# M1705X.net
KiCad netlist of a schematic drawn in EAGLE
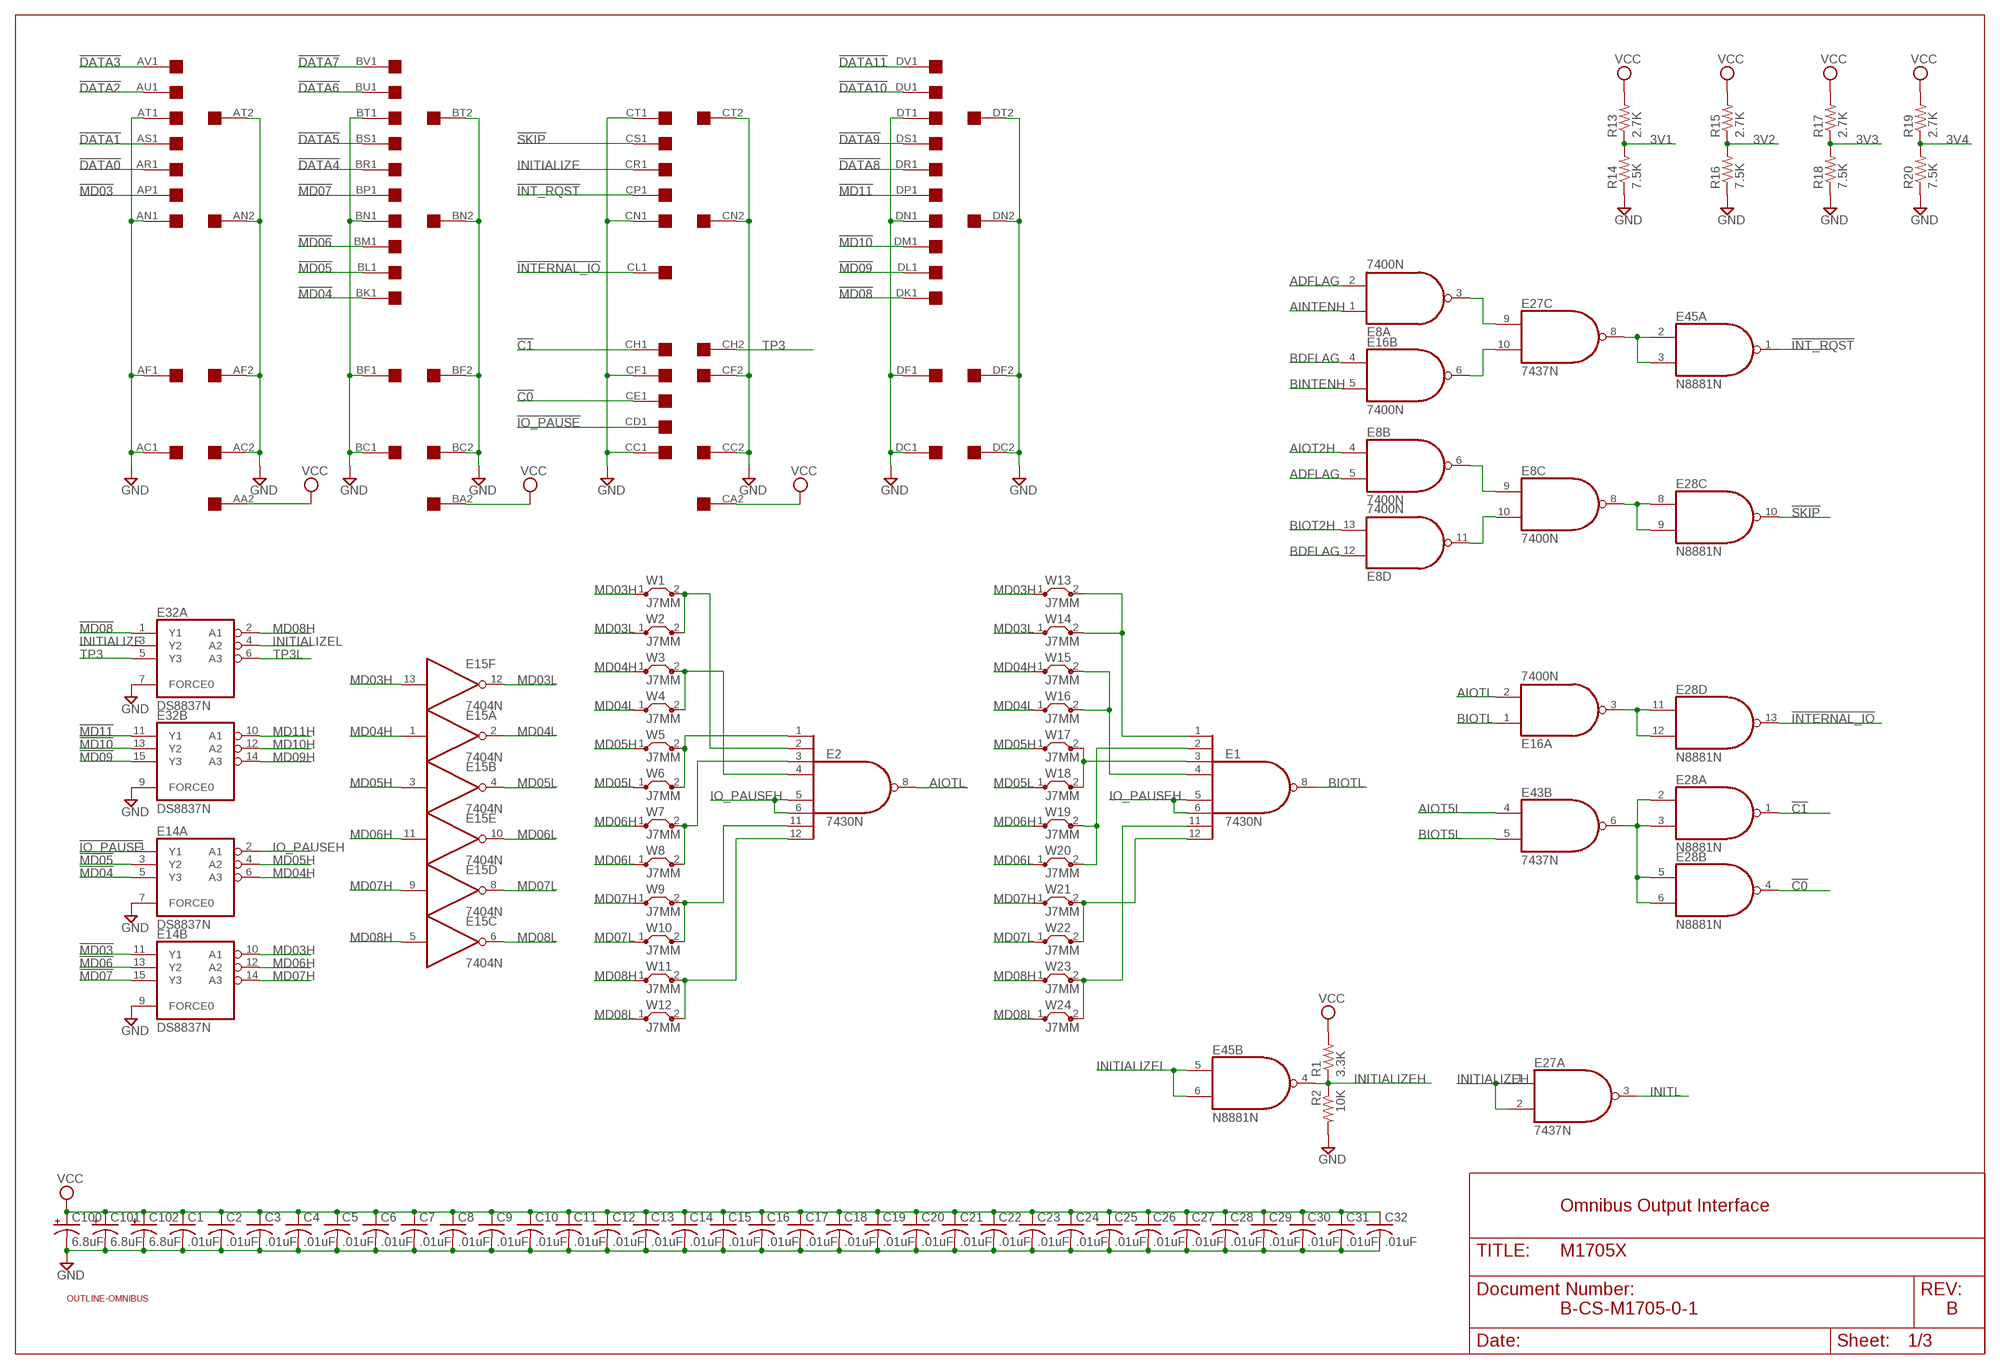
[diagram p0: schematic, sheet 1]
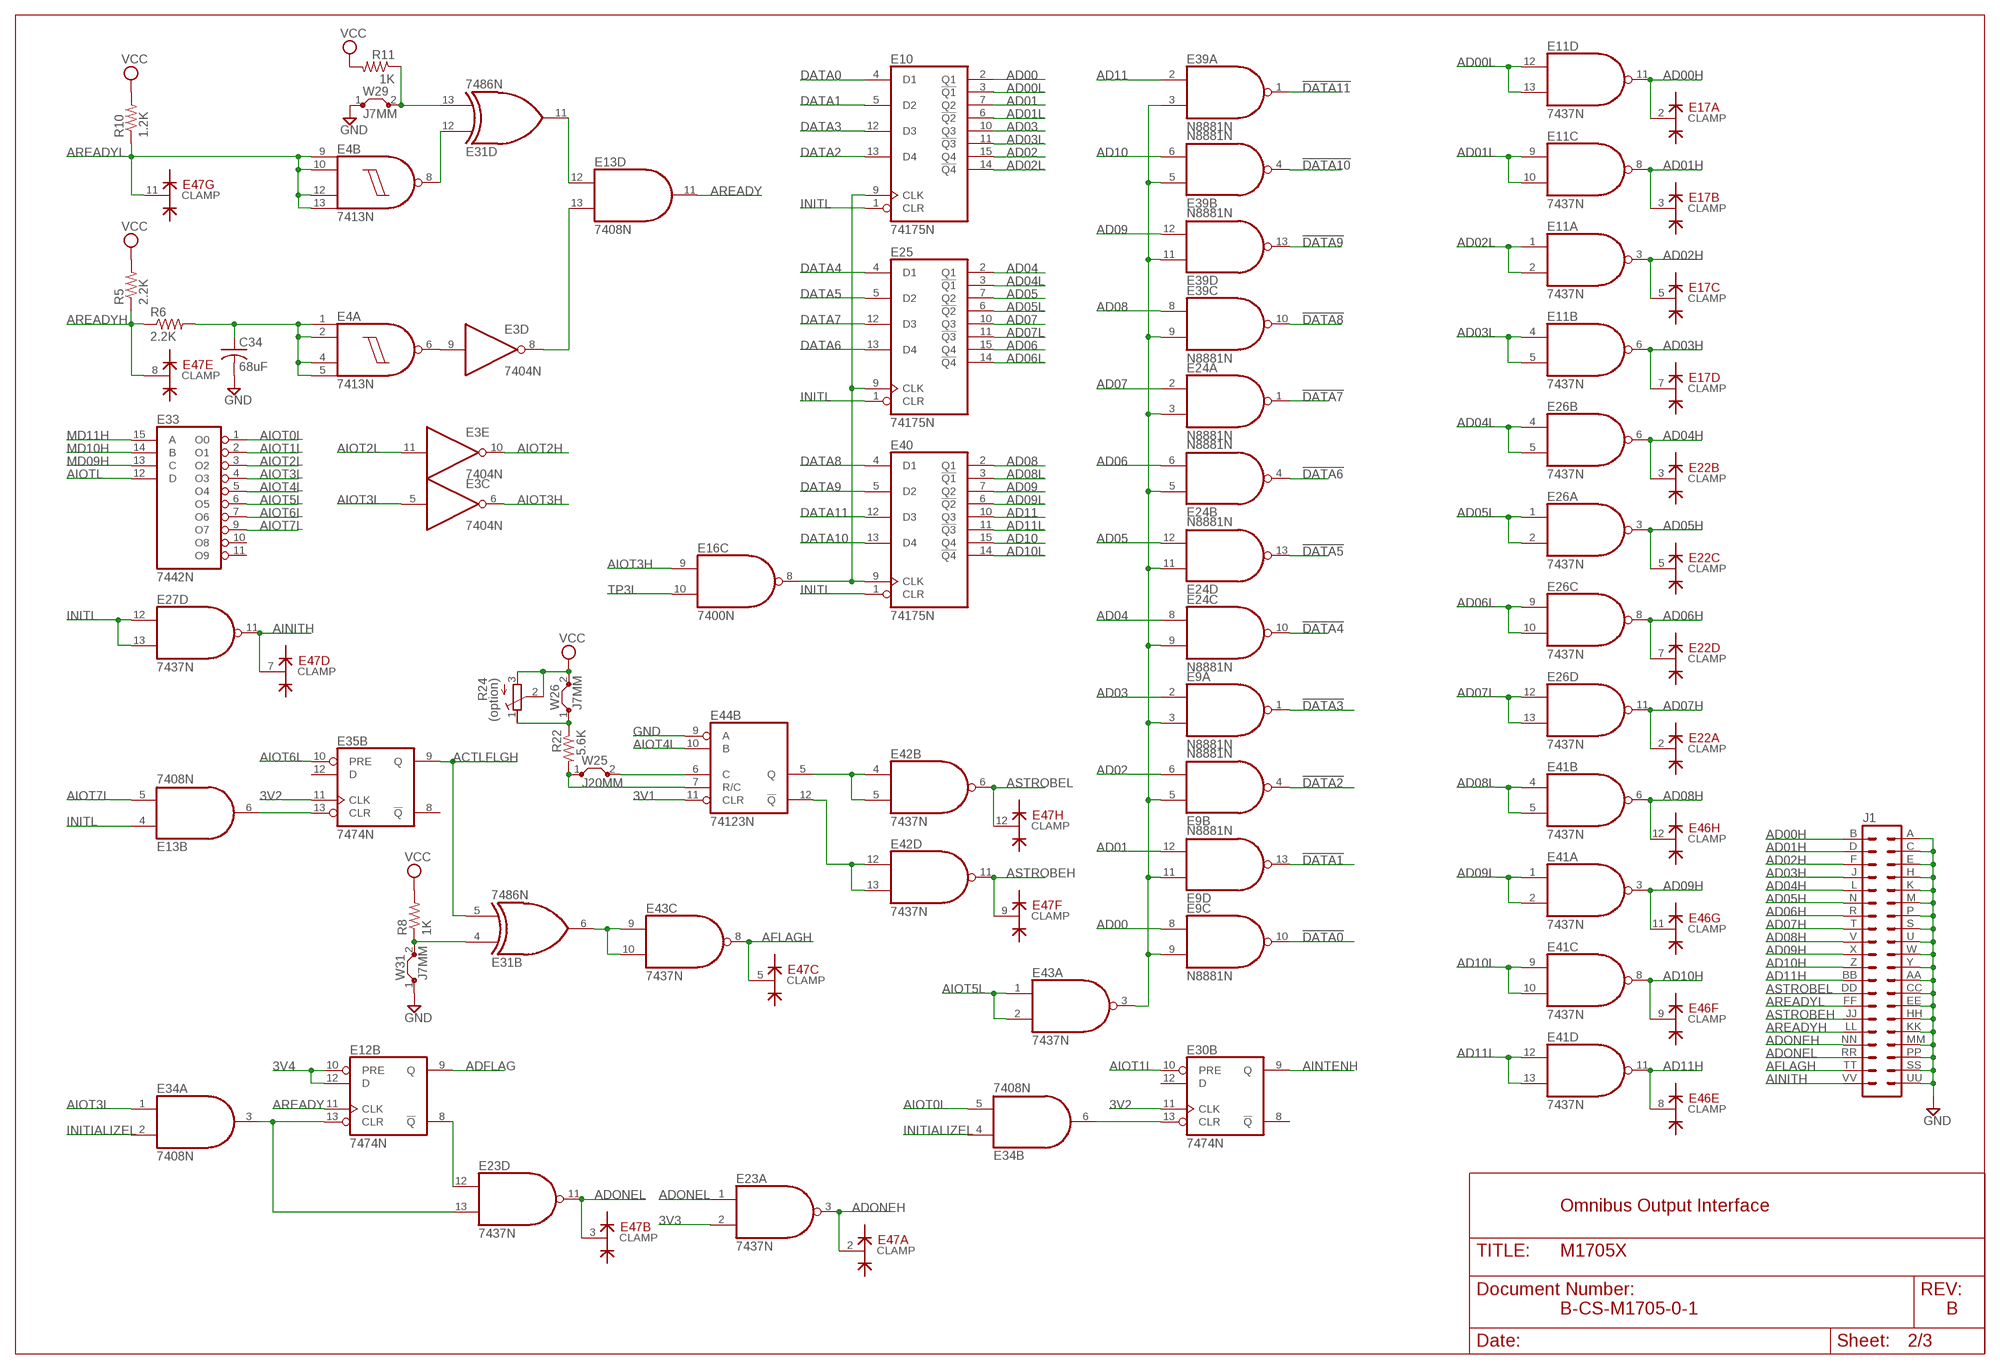
[diagram p1: schematic, sheet 2]
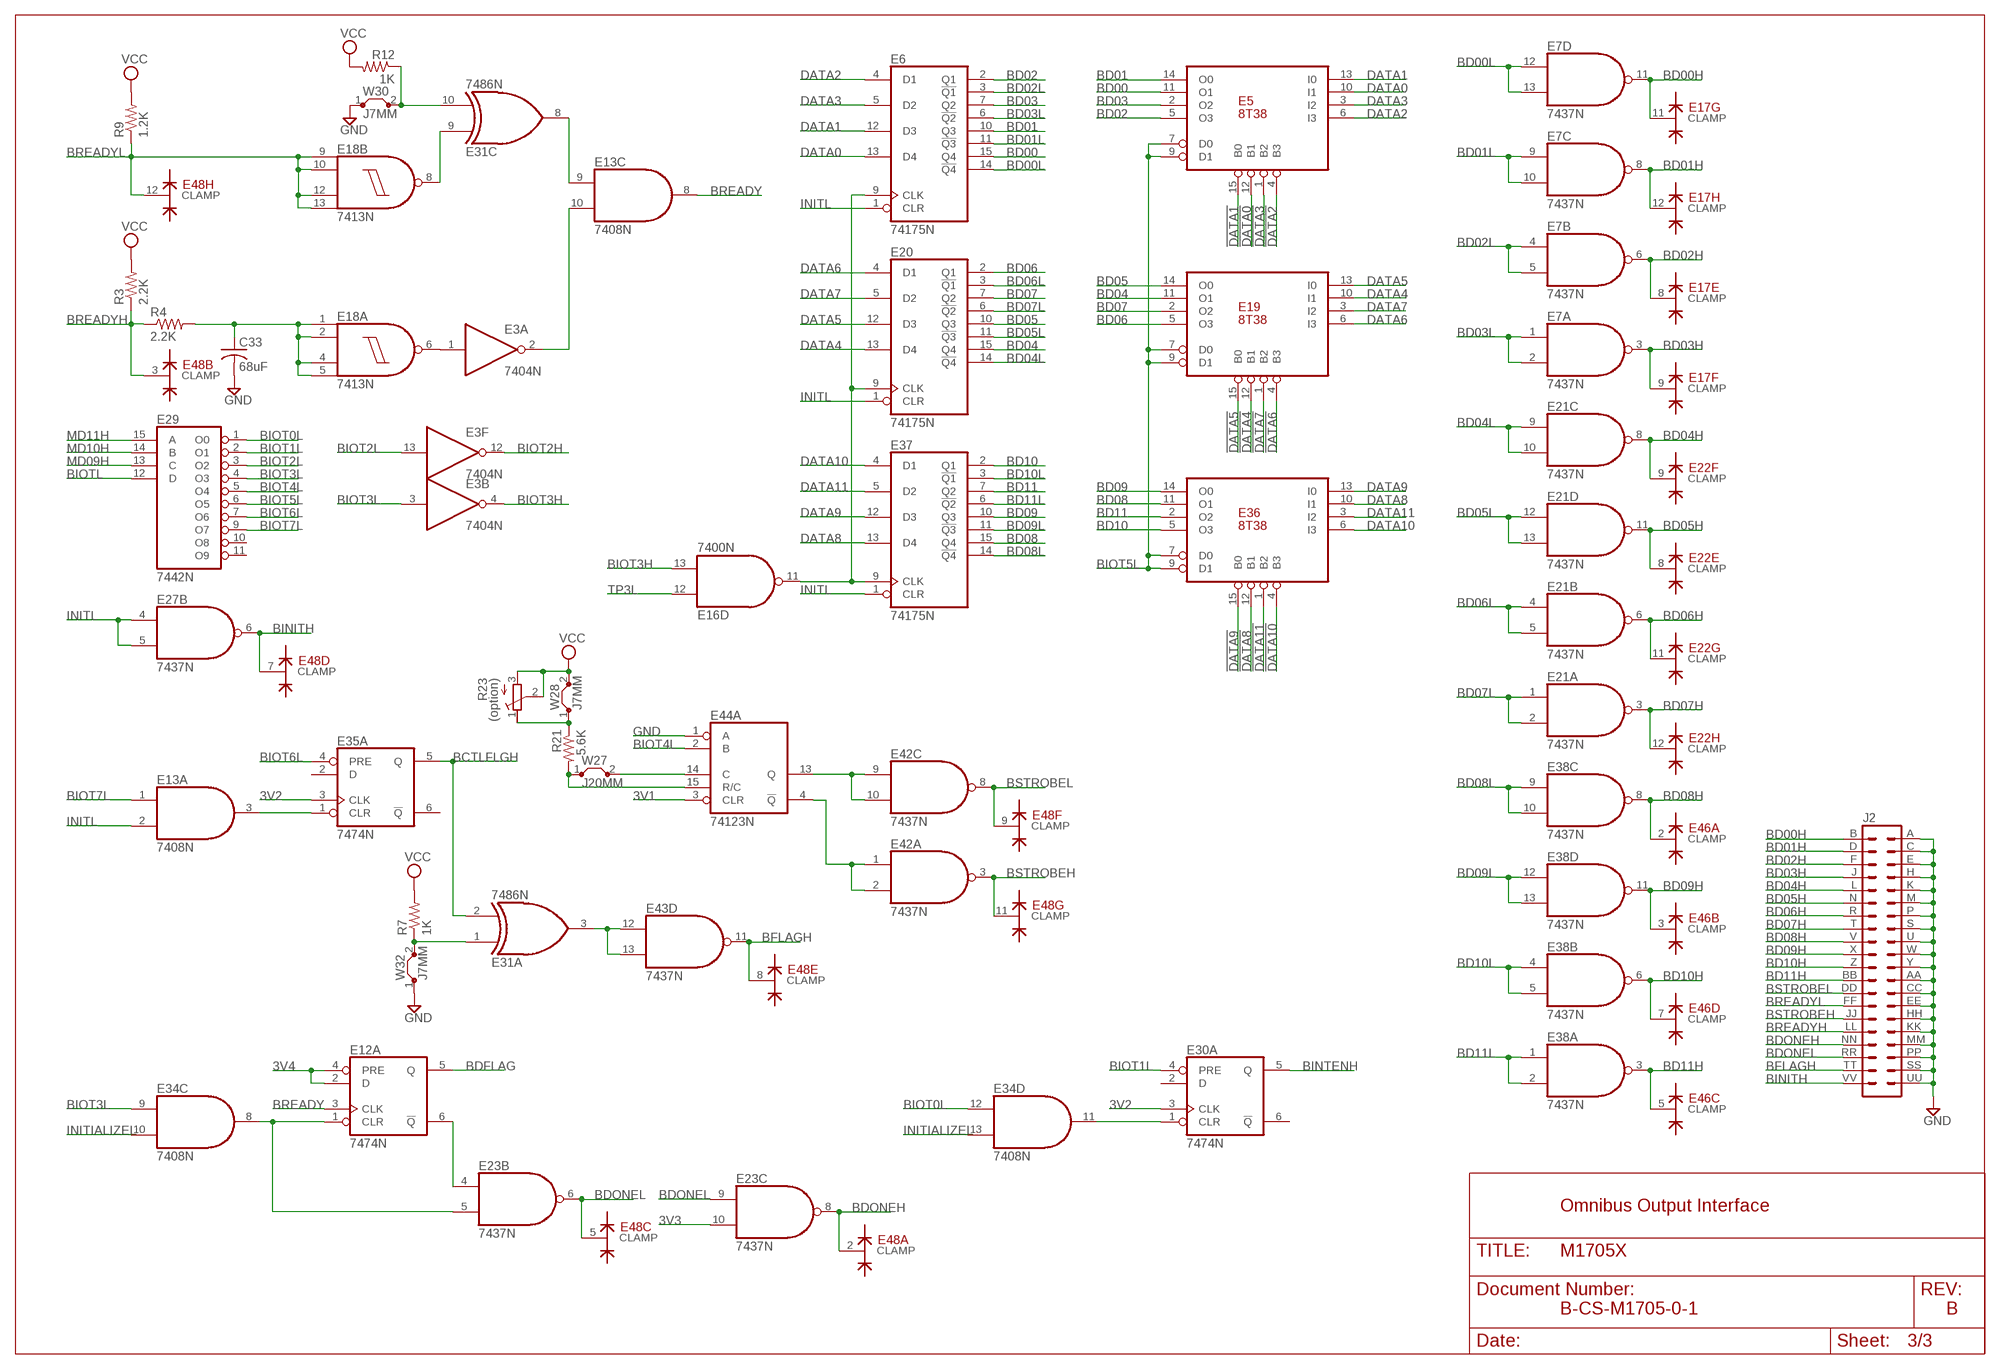
[diagram p2: schematic, sheet 3]

(export (version "E")
  (design (tool "Eeschema 10.0.6"))
  (components
    (comp (ref "C1")
      (value ".01uF")
      (footprint "eagle-import:C075-032X103")
      (libsource (lib "eagle-import") (part "C-US075-032X103"))
    )
    (comp (ref "C2")
      (value ".01uF")
      (footprint "eagle-import:C075-032X103")
      (libsource (lib "eagle-import") (part "C-US075-032X103"))
    )
    (comp (ref "C3")
      (value ".01uF")
      (footprint "eagle-import:C075-032X103")
      (libsource (lib "eagle-import") (part "C-US075-032X103"))
    )
    (comp (ref "C4")
      (value ".01uF")
      (footprint "eagle-import:C075-032X103")
      (libsource (lib "eagle-import") (part "C-US075-032X103"))
    )
    (comp (ref "C5")
      (value ".01uF")
      (footprint "eagle-import:C075-032X103")
      (libsource (lib "eagle-import") (part "C-US075-032X103"))
    )
    (comp (ref "C6")
      (value ".01uF")
      (footprint "eagle-import:C075-032X103")
      (libsource (lib "eagle-import") (part "C-US075-032X103"))
    )
    (comp (ref "C7")
      (value ".01uF")
      (footprint "eagle-import:C075-032X103")
      (libsource (lib "eagle-import") (part "C-US075-032X103"))
    )
    (comp (ref "C8")
      (value ".01uF")
      (footprint "eagle-import:C075-032X103")
      (libsource (lib "eagle-import") (part "C-US075-032X103"))
    )
    (comp (ref "C9")
      (value ".01uF")
      (footprint "eagle-import:C075-032X103")
      (libsource (lib "eagle-import") (part "C-US075-032X103"))
    )
    (comp (ref "C10")
      (value ".01uF")
      (footprint "eagle-import:C075-032X103")
      (libsource (lib "eagle-import") (part "C-US075-032X103"))
    )
    (comp (ref "C11")
      (value ".01uF")
      (footprint "eagle-import:C075-032X103")
      (libsource (lib "eagle-import") (part "C-US075-032X103"))
    )
    (comp (ref "C12")
      (value ".01uF")
      (footprint "eagle-import:C075-032X103")
      (libsource (lib "eagle-import") (part "C-US075-032X103"))
    )
    (comp (ref "C13")
      (value ".01uF")
      (footprint "eagle-import:C075-032X103")
      (libsource (lib "eagle-import") (part "C-US075-032X103"))
    )
    (comp (ref "C14")
      (value ".01uF")
      (footprint "eagle-import:C075-032X103")
      (libsource (lib "eagle-import") (part "C-US075-032X103"))
    )
    (comp (ref "C15")
      (value ".01uF")
      (footprint "eagle-import:C075-032X103")
      (libsource (lib "eagle-import") (part "C-US075-032X103"))
    )
    (comp (ref "C16")
      (value ".01uF")
      (footprint "eagle-import:C075-032X103")
      (libsource (lib "eagle-import") (part "C-US075-032X103"))
    )
    (comp (ref "C17")
      (value ".01uF")
      (footprint "eagle-import:C075-032X103")
      (libsource (lib "eagle-import") (part "C-US075-032X103"))
    )
    (comp (ref "C18")
      (value ".01uF")
      (footprint "eagle-import:C075-032X103")
      (libsource (lib "eagle-import") (part "C-US075-032X103"))
    )
    (comp (ref "C19")
      (value ".01uF")
      (footprint "eagle-import:C075-032X103")
      (libsource (lib "eagle-import") (part "C-US075-032X103"))
    )
    (comp (ref "C20")
      (value ".01uF")
      (footprint "eagle-import:C075-032X103")
      (libsource (lib "eagle-import") (part "C-US075-032X103"))
    )
    (comp (ref "C21")
      (value ".01uF")
      (footprint "eagle-import:C075-032X103")
      (libsource (lib "eagle-import") (part "C-US075-032X103"))
    )
    (comp (ref "C22")
      (value ".01uF")
      (footprint "eagle-import:C075-032X103")
      (libsource (lib "eagle-import") (part "C-US075-032X103"))
    )
    (comp (ref "C23")
      (value ".01uF")
      (footprint "eagle-import:C075-032X103")
      (libsource (lib "eagle-import") (part "C-US075-032X103"))
    )
    (comp (ref "C24")
      (value ".01uF")
      (footprint "eagle-import:C075-032X103")
      (libsource (lib "eagle-import") (part "C-US075-032X103"))
    )
    (comp (ref "C25")
      (value ".01uF")
      (footprint "eagle-import:C075-032X103")
      (libsource (lib "eagle-import") (part "C-US075-032X103"))
    )
    (comp (ref "C26")
      (value ".01uF")
      (footprint "eagle-import:C075-032X103")
      (libsource (lib "eagle-import") (part "C-US075-032X103"))
    )
    (comp (ref "C27")
      (value ".01uF")
      (footprint "eagle-import:C075-032X103")
      (libsource (lib "eagle-import") (part "C-US075-032X103"))
    )
    (comp (ref "C28")
      (value ".01uF")
      (footprint "eagle-import:C075-032X103")
      (libsource (lib "eagle-import") (part "C-US075-032X103"))
    )
    (comp (ref "C29")
      (value ".01uF")
      (footprint "eagle-import:C075-032X103")
      (libsource (lib "eagle-import") (part "C-US075-032X103"))
    )
    (comp (ref "C30")
      (value ".01uF")
      (footprint "eagle-import:C075-032X103")
      (libsource (lib "eagle-import") (part "C-US075-032X103"))
    )
    (comp (ref "C31")
      (value ".01uF")
      (footprint "eagle-import:C075-032X103")
      (libsource (lib "eagle-import") (part "C-US075-032X103"))
    )
    (comp (ref "C32")
      (value ".01uF")
      (footprint "eagle-import:C075-032X103")
      (libsource (lib "eagle-import") (part "C-US075-032X103"))
    )
    (comp (ref "C100")
      (value "6.8uF")
      (footprint "eagle-import:E12-8")
      (libsource (lib "eagle-import") (part "CPOL-USE20-8AXIAL"))
    )
    (comp (ref "C101")
      (value "6.8uF")
      (footprint "eagle-import:E12-8")
      (libsource (lib "eagle-import") (part "CPOL-USE20-8AXIAL"))
    )
    (comp (ref "C102")
      (value "6.8uF")
      (footprint "eagle-import:E12-8")
      (libsource (lib "eagle-import") (part "CPOL-USE20-8AXIAL"))
    )
    (comp (ref "E1")
      (value "7430N")
      (footprint "eagle-import:DIL14")
      (libsource (lib "eagle-import") (part "7430N"))
    )
    (comp (ref "E2")
      (value "7430N")
      (footprint "eagle-import:DIL14")
      (libsource (lib "eagle-import") (part "7430N"))
    )
    (comp (ref "E8")
      (value "7400N")
      (footprint "eagle-import:DIL14")
      (libsource (lib "eagle-import") (part "7400N"))
    )
    (comp (ref "E14")
      (value "DS8837N")
      (footprint "eagle-import:DIL16")
      (libsource (lib "eagle-import") (part "DS8837N"))
    )
    (comp (ref "E15")
      (value "7404N")
      (footprint "eagle-import:DIL14")
      (libsource (lib "eagle-import") (part "7404N"))
    )
    (comp (ref "E16")
      (value "7400N")
      (footprint "eagle-import:DIL14")
      (libsource (lib "eagle-import") (part "7400N"))
    )
    (comp (ref "E27")
      (value "7437N")
      (footprint "eagle-import:DIL14")
      (libsource (lib "eagle-import") (part "7437N"))
    )
    (comp (ref "E28")
      (value "N8881N")
      (footprint "eagle-import:DIL14")
      (libsource (lib "eagle-import") (part "N8881N"))
    )
    (comp (ref "E32")
      (value "DS8837N")
      (footprint "eagle-import:DIL16")
      (libsource (lib "eagle-import") (part "DS8837N"))
    )
    (comp (ref "E43")
      (value "7437N")
      (footprint "eagle-import:DIL14")
      (libsource (lib "eagle-import") (part "7437N"))
    )
    (comp (ref "E45")
      (value "N8881N")
      (footprint "eagle-import:DIL14")
      (libsource (lib "eagle-import") (part "N8881N"))
    )
    (comp (ref "R1")
      (value "3.3K")
      (footprint "eagle-import:0207_10")
      (libsource (lib "eagle-import") (part "R-US_0207/10"))
    )
    (comp (ref "R2")
      (value "10K")
      (footprint "eagle-import:0207_10")
      (libsource (lib "eagle-import") (part "R-US_0207/10"))
    )
    (comp (ref "R13")
      (value "2.7K")
      (footprint "eagle-import:0207_10")
      (libsource (lib "eagle-import") (part "R-US_0207/10"))
    )
    (comp (ref "R14")
      (value "7.5K")
      (footprint "eagle-import:0207_10")
      (libsource (lib "eagle-import") (part "R-US_0207/10"))
    )
    (comp (ref "R15")
      (value "2.7K")
      (footprint "eagle-import:0207_10")
      (libsource (lib "eagle-import") (part "R-US_0207/10"))
    )
    (comp (ref "R16")
      (value "7.5K")
      (footprint "eagle-import:0207_10")
      (libsource (lib "eagle-import") (part "R-US_0207/10"))
    )
    (comp (ref "R17")
      (value "2.7K")
      (footprint "eagle-import:0207_10")
      (libsource (lib "eagle-import") (part "R-US_0207/10"))
    )
    (comp (ref "R18")
      (value "7.5K")
      (footprint "eagle-import:0207_10")
      (libsource (lib "eagle-import") (part "R-US_0207/10"))
    )
    (comp (ref "R19")
      (value "2.7K")
      (footprint "eagle-import:0207_10")
      (libsource (lib "eagle-import") (part "R-US_0207/10"))
    )
    (comp (ref "R20")
      (value "7.5K")
      (footprint "eagle-import:0207_10")
      (libsource (lib "eagle-import") (part "R-US_0207/10"))
    )
    (comp (ref "U$2")
      (value "QUAD")
      (footprint "eagle-import:EDGE-CON8")
      (libsource (lib "eagle-import") (part "QUAD"))
    )
    (comp (ref "U$4")
      (value "OUTLINE-OMNIBUS")
      (footprint "eagle-import:OMNIBUS")
      (libsource (lib "eagle-import") (part "OUTLINE-OMNIBUS"))
    )
    (comp (ref "W1")
      (value "J7MM")
      (footprint "eagle-import:07")
      (libsource (lib "eagle-import") (part "J7MM"))
    )
    (comp (ref "W2")
      (value "J7MM")
      (footprint "eagle-import:07")
      (libsource (lib "eagle-import") (part "J7MM"))
    )
    (comp (ref "W3")
      (value "J7MM")
      (footprint "eagle-import:07")
      (libsource (lib "eagle-import") (part "J7MM"))
    )
    (comp (ref "W4")
      (value "J7MM")
      (footprint "eagle-import:07")
      (libsource (lib "eagle-import") (part "J7MM"))
    )
    (comp (ref "W5")
      (value "J7MM")
      (footprint "eagle-import:07")
      (libsource (lib "eagle-import") (part "J7MM"))
    )
    (comp (ref "W6")
      (value "J7MM")
      (footprint "eagle-import:07")
      (libsource (lib "eagle-import") (part "J7MM"))
    )
    (comp (ref "W7")
      (value "J7MM")
      (footprint "eagle-import:07")
      (libsource (lib "eagle-import") (part "J7MM"))
    )
    (comp (ref "W8")
      (value "J7MM")
      (footprint "eagle-import:07")
      (libsource (lib "eagle-import") (part "J7MM"))
    )
    (comp (ref "W9")
      (value "J7MM")
      (footprint "eagle-import:07")
      (libsource (lib "eagle-import") (part "J7MM"))
    )
    (comp (ref "W10")
      (value "J7MM")
      (footprint "eagle-import:07")
      (libsource (lib "eagle-import") (part "J7MM"))
    )
    (comp (ref "W11")
      (value "J7MM")
      (footprint "eagle-import:07")
      (libsource (lib "eagle-import") (part "J7MM"))
    )
    (comp (ref "W12")
      (value "J7MM")
      (footprint "eagle-import:07")
      (libsource (lib "eagle-import") (part "J7MM"))
    )
    (comp (ref "W13")
      (value "J7MM")
      (footprint "eagle-import:07")
      (libsource (lib "eagle-import") (part "J7MM"))
    )
    (comp (ref "W14")
      (value "J7MM")
      (footprint "eagle-import:07")
      (libsource (lib "eagle-import") (part "J7MM"))
    )
    (comp (ref "W15")
      (value "J7MM")
      (footprint "eagle-import:07")
      (libsource (lib "eagle-import") (part "J7MM"))
    )
    (comp (ref "W16")
      (value "J7MM")
      (footprint "eagle-import:07")
      (libsource (lib "eagle-import") (part "J7MM"))
    )
    (comp (ref "W17")
      (value "J7MM")
      (footprint "eagle-import:07")
      (libsource (lib "eagle-import") (part "J7MM"))
    )
    (comp (ref "W18")
      (value "J7MM")
      (footprint "eagle-import:07")
      (libsource (lib "eagle-import") (part "J7MM"))
    )
    (comp (ref "W19")
      (value "J7MM")
      (footprint "eagle-import:07")
      (libsource (lib "eagle-import") (part "J7MM"))
    )
    (comp (ref "W20")
      (value "J7MM")
      (footprint "eagle-import:07")
      (libsource (lib "eagle-import") (part "J7MM"))
    )
    (comp (ref "W21")
      (value "J7MM")
      (footprint "eagle-import:07")
      (libsource (lib "eagle-import") (part "J7MM"))
    )
    (comp (ref "W22")
      (value "J7MM")
      (footprint "eagle-import:07")
      (libsource (lib "eagle-import") (part "J7MM"))
    )
    (comp (ref "W23")
      (value "J7MM")
      (footprint "eagle-import:07")
      (libsource (lib "eagle-import") (part "J7MM"))
    )
    (comp (ref "W24")
      (value "J7MM")
      (footprint "eagle-import:07")
      (libsource (lib "eagle-import") (part "J7MM"))
    )
    (comp (ref "C34")
      (value "68uF")
      (footprint "eagle-import:C102-043X133")
      (libsource (lib "eagle-import") (part "C-US102-043X133"))
    )
    (comp (ref "E3")
      (value "7404N")
      (footprint "eagle-import:DIL14")
      (libsource (lib "eagle-import") (part "7404N"))
    )
    (comp (ref "E4")
      (value "7413N")
      (footprint "eagle-import:DIL14")
      (libsource (lib "eagle-import") (part "7413N"))
    )
    (comp (ref "E9")
      (value "N8881N")
      (footprint "eagle-import:DIL14")
      (libsource (lib "eagle-import") (part "N8881N"))
    )
    (comp (ref "E10")
      (value "74175N")
      (footprint "eagle-import:DIL16")
      (libsource (lib "eagle-import") (part "74175N"))
    )
    (comp (ref "E11")
      (value "7437N")
      (footprint "eagle-import:DIL14")
      (libsource (lib "eagle-import") (part "7437N"))
    )
    (comp (ref "E12")
      (value "7474N")
      (footprint "eagle-import:DIL14")
      (libsource (lib "eagle-import") (part "7474NS"))
    )
    (comp (ref "E13")
      (value "7408N")
      (footprint "eagle-import:DIL14")
      (libsource (lib "eagle-import") (part "7408NLS"))
    )
    (comp (ref "E17")
      (value "DEC2501")
      (footprint "eagle-import:DIL14")
      (libsource (lib "eagle-import") (part "DEC2501"))
    )
    (comp (ref "E22")
      (value "DEC2501")
      (footprint "eagle-import:DIL14")
      (libsource (lib "eagle-import") (part "DEC2501"))
    )
    (comp (ref "E23")
      (value "7437N")
      (footprint "eagle-import:DIL14")
      (libsource (lib "eagle-import") (part "7437N"))
    )
    (comp (ref "E24")
      (value "N8881N")
      (footprint "eagle-import:DIL14")
      (libsource (lib "eagle-import") (part "N8881N"))
    )
    (comp (ref "E25")
      (value "74175N")
      (footprint "eagle-import:DIL16")
      (libsource (lib "eagle-import") (part "74175N"))
    )
    (comp (ref "E26")
      (value "7437N")
      (footprint "eagle-import:DIL14")
      (libsource (lib "eagle-import") (part "7437N"))
    )
    (comp (ref "E30")
      (value "7474N")
      (footprint "eagle-import:DIL14")
      (libsource (lib "eagle-import") (part "7474NS"))
    )
    (comp (ref "E31")
      (value "7486N")
      (footprint "eagle-import:DIL14")
      (libsource (lib "eagle-import") (part "7486N"))
    )
    (comp (ref "E33")
      (value "7442N")
      (footprint "eagle-import:DIL16")
      (libsource (lib "eagle-import") (part "7442NLS"))
    )
    (comp (ref "E34")
      (value "7408N")
      (footprint "eagle-import:DIL14")
      (libsource (lib "eagle-import") (part "7408NLS"))
    )
    (comp (ref "E35")
      (value "7474N")
      (footprint "eagle-import:DIL14")
      (libsource (lib "eagle-import") (part "7474NS"))
    )
    (comp (ref "E39")
      (value "N8881N")
      (footprint "eagle-import:DIL14")
      (libsource (lib "eagle-import") (part "N8881N"))
    )
    (comp (ref "E40")
      (value "74175N")
      (footprint "eagle-import:DIL16")
      (libsource (lib "eagle-import") (part "74175N"))
    )
    (comp (ref "E41")
      (value "7437N")
      (footprint "eagle-import:DIL14")
      (libsource (lib "eagle-import") (part "7437N"))
    )
    (comp (ref "E42")
      (value "7437N")
      (footprint "eagle-import:DIL14")
      (libsource (lib "eagle-import") (part "7437N"))
    )
    (comp (ref "E44")
      (value "74123N")
      (footprint "eagle-import:DIL16")
      (libsource (lib "eagle-import") (part "74123N"))
    )
    (comp (ref "E46")
      (value "DEC2501")
      (footprint "eagle-import:DIL14")
      (libsource (lib "eagle-import") (part "DEC2501"))
    )
    (comp (ref "E47")
      (value "DEC2501")
      (footprint "eagle-import:DIL14")
      (libsource (lib "eagle-import") (part "DEC2501"))
    )
    (comp (ref "J1")
      (value "DEC40PINH")
      (footprint "eagle-import:DEC40PINH")
      (libsource (lib "eagle-import") (part "DEC40PINH"))
    )
    (comp (ref "R5")
      (value "2.2K")
      (footprint "eagle-import:0207_10")
      (libsource (lib "eagle-import") (part "R-US_0207/10"))
    )
    (comp (ref "R6")
      (value "2.2K")
      (footprint "eagle-import:0207_10")
      (libsource (lib "eagle-import") (part "R-US_0207/10"))
    )
    (comp (ref "R8")
      (value "1K")
      (footprint "eagle-import:0207_10")
      (libsource (lib "eagle-import") (part "R-US_0207/10"))
    )
    (comp (ref "R10")
      (value "1.2K")
      (footprint "eagle-import:0207_10")
      (libsource (lib "eagle-import") (part "R-US_0207/10"))
    )
    (comp (ref "R11")
      (value "1K")
      (footprint "eagle-import:0207_10")
      (libsource (lib "eagle-import") (part "R-US_0207/10"))
    )
    (comp (ref "R22")
      (value "5.6K")
      (footprint "eagle-import:0207_10")
      (libsource (lib "eagle-import") (part "R-US_0207/10"))
    )
    (comp (ref "R24")
      (value "(option)")
      (footprint "eagle-import:3006Y")
      (libsource (lib "eagle-import") (part "275P"))
    )
    (comp (ref "W25")
      (value "J20MM")
      (footprint "eagle-import:20")
      (libsource (lib "eagle-import") (part "J20MM"))
    )
    (comp (ref "W26")
      (value "J7MM")
      (footprint "eagle-import:07")
      (libsource (lib "eagle-import") (part "J7MM"))
    )
    (comp (ref "W29")
      (value "J7MM")
      (footprint "eagle-import:07")
      (libsource (lib "eagle-import") (part "J7MM"))
    )
    (comp (ref "W31")
      (value "J7MM")
      (footprint "eagle-import:07")
      (libsource (lib "eagle-import") (part "J7MM"))
    )
    (comp (ref "C33")
      (value "68uF")
      (footprint "eagle-import:C102-043X133")
      (libsource (lib "eagle-import") (part "C-US102-043X133"))
    )
    (comp (ref "E5")
      (value "8T38")
      (footprint "eagle-import:DIL16")
      (libsource (lib "eagle-import") (part "DS8641N"))
    )
    (comp (ref "E6")
      (value "74175N")
      (footprint "eagle-import:DIL16")
      (libsource (lib "eagle-import") (part "74175N"))
    )
    (comp (ref "E7")
      (value "7437N")
      (footprint "eagle-import:DIL14")
      (libsource (lib "eagle-import") (part "7437N"))
    )
    (comp (ref "E18")
      (value "7413N")
      (footprint "eagle-import:DIL14")
      (libsource (lib "eagle-import") (part "7413N"))
    )
    (comp (ref "E19")
      (value "8T38")
      (footprint "eagle-import:DIL16")
      (libsource (lib "eagle-import") (part "DS8641N"))
    )
    (comp (ref "E20")
      (value "74175N")
      (footprint "eagle-import:DIL16")
      (libsource (lib "eagle-import") (part "74175N"))
    )
    (comp (ref "E21")
      (value "7437N")
      (footprint "eagle-import:DIL14")
      (libsource (lib "eagle-import") (part "7437N"))
    )
    (comp (ref "E29")
      (value "7442N")
      (footprint "eagle-import:DIL16")
      (libsource (lib "eagle-import") (part "7442NLS"))
    )
    (comp (ref "E36")
      (value "8T38")
      (footprint "eagle-import:DIL16")
      (libsource (lib "eagle-import") (part "DS8641N"))
    )
    (comp (ref "E37")
      (value "74175N")
      (footprint "eagle-import:DIL16")
      (libsource (lib "eagle-import") (part "74175N"))
    )
    (comp (ref "E38")
      (value "7437N")
      (footprint "eagle-import:DIL14")
      (libsource (lib "eagle-import") (part "7437N"))
    )
    (comp (ref "E48")
      (value "DEC2501")
      (footprint "eagle-import:DIL14")
      (libsource (lib "eagle-import") (part "DEC2501"))
    )
    (comp (ref "J2")
      (value "DEC40PINH")
      (footprint "eagle-import:DEC40PINH")
      (libsource (lib "eagle-import") (part "DEC40PINH"))
    )
    (comp (ref "R3")
      (value "2.2K")
      (footprint "eagle-import:0207_10")
      (libsource (lib "eagle-import") (part "R-US_0207/10"))
    )
    (comp (ref "R4")
      (value "2.2K")
      (footprint "eagle-import:0207_10")
      (libsource (lib "eagle-import") (part "R-US_0207/10"))
    )
    (comp (ref "R7")
      (value "1K")
      (footprint "eagle-import:0207_10")
      (libsource (lib "eagle-import") (part "R-US_0207/10"))
    )
    (comp (ref "R9")
      (value "1.2K")
      (footprint "eagle-import:0207_10")
      (libsource (lib "eagle-import") (part "R-US_0207/10"))
    )
    (comp (ref "R12")
      (value "1K")
      (footprint "eagle-import:0207_10")
      (libsource (lib "eagle-import") (part "R-US_0207/10"))
    )
    (comp (ref "R21")
      (value "5.6K")
      (footprint "eagle-import:0207_10")
      (libsource (lib "eagle-import") (part "R-US_0207/10"))
    )
    (comp (ref "R23")
      (value "(option)")
      (footprint "eagle-import:3006Y")
      (libsource (lib "eagle-import") (part "275P"))
    )
    (comp (ref "W27")
      (value "J20MM")
      (footprint "eagle-import:20")
      (libsource (lib "eagle-import") (part "J20MM"))
    )
    (comp (ref "W28")
      (value "J7MM")
      (footprint "eagle-import:07")
      (libsource (lib "eagle-import") (part "J7MM"))
    )
    (comp (ref "W30")
      (value "J7MM")
      (footprint "eagle-import:07")
      (libsource (lib "eagle-import") (part "J7MM"))
    )
    (comp (ref "W32")
      (value "J7MM")
      (footprint "eagle-import:07")
      (libsource (lib "eagle-import") (part "J7MM"))
    )
  )
  (nets
    (net (code "1") (name "3V1") (class "Default")
      (node (ref "E44") (pin "11") (pinfunction "CLR_11") (pintype "input"))
      (node (ref "E44") (pin "3") (pinfunction "CLR_3") (pintype "input"))
      (node (ref "R13") (pin "1") (pinfunction "1_1") (pintype "passive"))
      (node (ref "R14") (pin "2") (pinfunction "2_2") (pintype "passive"))
    )
    (net (code "2") (name "3V2") (class "Default")
      (node (ref "E30") (pin "11") (pinfunction "CLK_11") (pintype "input"))
      (node (ref "E30") (pin "3") (pinfunction "CLK_3") (pintype "input"))
      (node (ref "E35") (pin "11") (pinfunction "CLK_11") (pintype "input"))
      (node (ref "E35") (pin "3") (pinfunction "CLK_3") (pintype "input"))
      (node (ref "R15") (pin "1") (pinfunction "1_1") (pintype "passive"))
      (node (ref "R16") (pin "2") (pinfunction "2_2") (pintype "passive"))
    )
    (net (code "3") (name "3V3") (class "Default")
      (node (ref "E23") (pin "10") (pinfunction "I1_10") (pintype "input"))
      (node (ref "E23") (pin "2") (pinfunction "I1_2") (pintype "input"))
      (node (ref "R17") (pin "1") (pinfunction "1_1") (pintype "passive"))
      (node (ref "R18") (pin "2") (pinfunction "2_2") (pintype "passive"))
    )
    (net (code "4") (name "3V4") (class "Default")
      (node (ref "E12") (pin "10") (pinfunction "PRE_10") (pintype "input"))
      (node (ref "E12") (pin "12") (pinfunction "D_12") (pintype "input"))
      (node (ref "E12") (pin "2") (pinfunction "D_2") (pintype "input"))
      (node (ref "E12") (pin "4") (pinfunction "PRE_4") (pintype "input"))
      (node (ref "R19") (pin "1") (pinfunction "1_1") (pintype "passive"))
      (node (ref "R20") (pin "2") (pinfunction "2_2") (pintype "passive"))
    )
    (net (code "5") (name "ACTLFLGH") (class "Default")
      (node (ref "E31") (pin "5") (pinfunction "I1_5") (pintype "input"))
      (node (ref "E35") (pin "9") (pinfunction "Q_9") (pintype "output"))
    )
    (net (code "6") (name "AD00") (class "Default")
      (node (ref "E10") (pin "2") (pinfunction "Q1_2") (pintype "output"))
      (node (ref "E9") (pin "8") (pinfunction "I0_8") (pintype "input"))
    )
    (net (code "7") (name "AD00H") (class "Default")
      (node (ref "E11") (pin "11") (pinfunction "O_11") (pintype "output"))
      (node (ref "E17") (pin "2") (pinfunction "CLAMP_2") (pintype "input"))
      (node (ref "J1") (pin "B") (pinfunction "2_B") (pintype "bidirectional"))
    )
    (net (code "8") (name "AD00L") (class "Default")
      (node (ref "E10") (pin "3") (pinfunction "~{Q1}_3") (pintype "output"))
      (node (ref "E11") (pin "12") (pinfunction "I0_12") (pintype "input"))
      (node (ref "E11") (pin "13") (pinfunction "I1_13") (pintype "input"))
    )
    (net (code "9") (name "AD01") (class "Default")
      (node (ref "E10") (pin "7") (pinfunction "Q2_7") (pintype "output"))
      (node (ref "E9") (pin "12") (pinfunction "I1_12") (pintype "input"))
    )
    (net (code "10") (name "AD01H") (class "Default")
      (node (ref "E11") (pin "8") (pinfunction "O_8") (pintype "output"))
      (node (ref "E17") (pin "3") (pinfunction "CLAMP_3") (pintype "input"))
      (node (ref "J1") (pin "D") (pinfunction "4_D") (pintype "bidirectional"))
    )
    (net (code "11") (name "AD01L") (class "Default")
      (node (ref "E10") (pin "6") (pinfunction "~{Q2}_6") (pintype "output"))
      (node (ref "E11") (pin "10") (pinfunction "I1_10") (pintype "input"))
      (node (ref "E11") (pin "9") (pinfunction "I0_9") (pintype "input"))
    )
    (net (code "12") (name "AD02") (class "Default")
      (node (ref "E10") (pin "15") (pinfunction "Q4_15") (pintype "output"))
      (node (ref "E9") (pin "6") (pinfunction "I1_6") (pintype "input"))
    )
    (net (code "13") (name "AD02H") (class "Default")
      (node (ref "E11") (pin "3") (pinfunction "O_3") (pintype "output"))
      (node (ref "E17") (pin "5") (pinfunction "CLAMP_5") (pintype "input"))
      (node (ref "J1") (pin "F") (pinfunction "6_F") (pintype "bidirectional"))
    )
    (net (code "14") (name "AD02L") (class "Default")
      (node (ref "E10") (pin "14") (pinfunction "~{Q4}_14") (pintype "output"))
      (node (ref "E11") (pin "1") (pinfunction "I0_1") (pintype "input"))
      (node (ref "E11") (pin "2") (pinfunction "I1_2") (pintype "input"))
    )
    (net (code "15") (name "AD03") (class "Default")
      (node (ref "E10") (pin "10") (pinfunction "Q3_10") (pintype "output"))
      (node (ref "E9") (pin "2") (pinfunction "I0_2") (pintype "input"))
    )
    (net (code "16") (name "AD03H") (class "Default")
      (node (ref "E11") (pin "6") (pinfunction "O_6") (pintype "output"))
      (node (ref "E17") (pin "7") (pinfunction "CLAMP_7") (pintype "input"))
      (node (ref "J1") (pin "J") (pinfunction "8_J") (pintype "bidirectional"))
    )
    (net (code "17") (name "AD03L") (class "Default")
      (node (ref "E10") (pin "11") (pinfunction "~{Q3}_11") (pintype "output"))
      (node (ref "E11") (pin "4") (pinfunction "I0_4") (pintype "input"))
      (node (ref "E11") (pin "5") (pinfunction "I1_5") (pintype "input"))
    )
    (net (code "18") (name "AD04") (class "Default")
      (node (ref "E24") (pin "8") (pinfunction "I0_8") (pintype "input"))
      (node (ref "E25") (pin "2") (pinfunction "Q1_2") (pintype "output"))
    )
    (net (code "19") (name "AD04H") (class "Default")
      (node (ref "E22") (pin "3") (pinfunction "CLAMP_3") (pintype "input"))
      (node (ref "E26") (pin "6") (pinfunction "O_6") (pintype "output"))
      (node (ref "J1") (pin "L") (pinfunction "10_L") (pintype "bidirectional"))
    )
    (net (code "20") (name "AD04L") (class "Default")
      (node (ref "E25") (pin "3") (pinfunction "~{Q1}_3") (pintype "output"))
      (node (ref "E26") (pin "4") (pinfunction "I0_4") (pintype "input"))
      (node (ref "E26") (pin "5") (pinfunction "I1_5") (pintype "input"))
    )
    (net (code "21") (name "AD05") (class "Default")
      (node (ref "E24") (pin "12") (pinfunction "I1_12") (pintype "input"))
      (node (ref "E25") (pin "7") (pinfunction "Q2_7") (pintype "output"))
    )
    (net (code "22") (name "AD05H") (class "Default")
      (node (ref "E22") (pin "5") (pinfunction "CLAMP_5") (pintype "input"))
      (node (ref "E26") (pin "3") (pinfunction "O_3") (pintype "output"))
      (node (ref "J1") (pin "N") (pinfunction "12_N") (pintype "bidirectional"))
    )
    (net (code "23") (name "AD05L") (class "Default")
      (node (ref "E25") (pin "6") (pinfunction "~{Q2}_6") (pintype "output"))
      (node (ref "E26") (pin "1") (pinfunction "I0_1") (pintype "input"))
      (node (ref "E26") (pin "2") (pinfunction "I1_2") (pintype "input"))
    )
    (net (code "24") (name "AD06") (class "Default")
      (node (ref "E24") (pin "6") (pinfunction "I1_6") (pintype "input"))
      (node (ref "E25") (pin "15") (pinfunction "Q4_15") (pintype "output"))
    )
    (net (code "25") (name "AD06H") (class "Default")
      (node (ref "E22") (pin "7") (pinfunction "CLAMP_7") (pintype "input"))
      (node (ref "E26") (pin "8") (pinfunction "O_8") (pintype "output"))
      (node (ref "J1") (pin "R") (pinfunction "14_R") (pintype "bidirectional"))
    )
    (net (code "26") (name "AD06L") (class "Default")
      (node (ref "E25") (pin "14") (pinfunction "~{Q4}_14") (pintype "output"))
      (node (ref "E26") (pin "10") (pinfunction "I1_10") (pintype "input"))
      (node (ref "E26") (pin "9") (pinfunction "I0_9") (pintype "input"))
    )
    (net (code "27") (name "AD07") (class "Default")
      (node (ref "E24") (pin "2") (pinfunction "I0_2") (pintype "input"))
      (node (ref "E25") (pin "10") (pinfunction "Q3_10") (pintype "output"))
    )
    (net (code "28") (name "AD07H") (class "Default")
      (node (ref "E22") (pin "2") (pinfunction "CLAMP_2") (pintype "input"))
      (node (ref "E26") (pin "11") (pinfunction "O_11") (pintype "output"))
      (node (ref "J1") (pin "T") (pinfunction "16_T") (pintype "bidirectional"))
    )
    (net (code "29") (name "AD07L") (class "Default")
      (node (ref "E25") (pin "11") (pinfunction "~{Q3}_11") (pintype "output"))
      (node (ref "E26") (pin "12") (pinfunction "I0_12") (pintype "input"))
      (node (ref "E26") (pin "13") (pinfunction "I1_13") (pintype "input"))
    )
    (net (code "30") (name "AD08") (class "Default")
      (node (ref "E39") (pin "8") (pinfunction "I0_8") (pintype "input"))
      (node (ref "E40") (pin "2") (pinfunction "Q1_2") (pintype "output"))
    )
    (net (code "31") (name "AD08H") (class "Default")
      (node (ref "E41") (pin "6") (pinfunction "O_6") (pintype "output"))
      (node (ref "E46") (pin "12") (pinfunction "CLAMP_12") (pintype "input"))
      (node (ref "J1") (pin "V") (pinfunction "18_V") (pintype "bidirectional"))
    )
    (net (code "32") (name "AD08L") (class "Default")
      (node (ref "E40") (pin "3") (pinfunction "~{Q1}_3") (pintype "output"))
      (node (ref "E41") (pin "4") (pinfunction "I0_4") (pintype "input"))
      (node (ref "E41") (pin "5") (pinfunction "I1_5") (pintype "input"))
    )
    (net (code "33") (name "AD09") (class "Default")
      (node (ref "E39") (pin "12") (pinfunction "I1_12") (pintype "input"))
      (node (ref "E40") (pin "7") (pinfunction "Q2_7") (pintype "output"))
    )
    (net (code "34") (name "AD09H") (class "Default")
      (node (ref "E41") (pin "3") (pinfunction "O_3") (pintype "output"))
      (node (ref "E46") (pin "11") (pinfunction "CLAMP_11") (pintype "input"))
      (node (ref "J1") (pin "X") (pinfunction "20_X") (pintype "bidirectional"))
    )
    (net (code "35") (name "AD09L") (class "Default")
      (node (ref "E40") (pin "6") (pinfunction "~{Q2}_6") (pintype "output"))
      (node (ref "E41") (pin "1") (pinfunction "I0_1") (pintype "input"))
      (node (ref "E41") (pin "2") (pinfunction "I1_2") (pintype "input"))
    )
    (net (code "36") (name "AD10") (class "Default")
      (node (ref "E39") (pin "6") (pinfunction "I1_6") (pintype "input"))
      (node (ref "E40") (pin "15") (pinfunction "Q4_15") (pintype "output"))
    )
    (net (code "37") (name "AD10H") (class "Default")
      (node (ref "E41") (pin "8") (pinfunction "O_8") (pintype "output"))
      (node (ref "E46") (pin "9") (pinfunction "CLAMP_9") (pintype "input"))
      (node (ref "J1") (pin "Z") (pinfunction "22_Z") (pintype "bidirectional"))
    )
    (net (code "38") (name "AD10L") (class "Default")
      (node (ref "E40") (pin "14") (pinfunction "~{Q4}_14") (pintype "output"))
      (node (ref "E41") (pin "10") (pinfunction "I1_10") (pintype "input"))
      (node (ref "E41") (pin "9") (pinfunction "I0_9") (pintype "input"))
    )
    (net (code "39") (name "AD11") (class "Default")
      (node (ref "E39") (pin "2") (pinfunction "I0_2") (pintype "input"))
      (node (ref "E40") (pin "10") (pinfunction "Q3_10") (pintype "output"))
    )
    (net (code "40") (name "AD11H") (class "Default")
      (node (ref "E41") (pin "11") (pinfunction "O_11") (pintype "output"))
      (node (ref "E46") (pin "8") (pinfunction "CLAMP_8") (pintype "input"))
      (node (ref "J1") (pin "BB") (pinfunction "24_BB") (pintype "bidirectional"))
    )
    (net (code "41") (name "AD11L") (class "Default")
      (node (ref "E40") (pin "11") (pinfunction "~{Q3}_11") (pintype "output"))
      (node (ref "E41") (pin "12") (pinfunction "I0_12") (pintype "input"))
      (node (ref "E41") (pin "13") (pinfunction "I1_13") (pintype "input"))
    )
    (net (code "42") (name "ADFLAG") (class "Default")
      (node (ref "E12") (pin "9") (pinfunction "Q_9") (pintype "output"))
      (node (ref "E8") (pin "2") (pinfunction "I1_2") (pintype "input"))
      (node (ref "E8") (pin "5") (pinfunction "I1_5") (pintype "input"))
    )
    (net (code "43") (name "ADONEH") (class "Default")
      (node (ref "E23") (pin "3") (pinfunction "O_3") (pintype "output"))
      (node (ref "E47") (pin "2") (pinfunction "CLAMP_2") (pintype "input"))
      (node (ref "J1") (pin "NN") (pinfunction "34_NN") (pintype "bidirectional"))
    )
    (net (code "44") (name "ADONEL") (class "Default")
      (node (ref "E23") (pin "1") (pinfunction "I0_1") (pintype "input"))
      (node (ref "E23") (pin "11") (pinfunction "O_11") (pintype "output"))
      (node (ref "E47") (pin "3") (pinfunction "CLAMP_3") (pintype "input"))
      (node (ref "J1") (pin "RR") (pinfunction "36_RR") (pintype "bidirectional"))
    )
    (net (code "45") (name "AFLAGH") (class "Default")
      (node (ref "E43") (pin "8") (pinfunction "O_8") (pintype "output"))
      (node (ref "E47") (pin "5") (pinfunction "CLAMP_5") (pintype "input"))
      (node (ref "J1") (pin "TT") (pinfunction "38_TT") (pintype "bidirectional"))
    )
    (net (code "46") (name "AINITH") (class "Default")
      (node (ref "E27") (pin "11") (pinfunction "O_11") (pintype "output"))
      (node (ref "E47") (pin "7") (pinfunction "CLAMP_7") (pintype "input"))
      (node (ref "J1") (pin "VV") (pinfunction "40_VV") (pintype "bidirectional"))
    )
    (net (code "47") (name "AINTENH") (class "Default")
      (node (ref "E30") (pin "9") (pinfunction "Q_9") (pintype "output"))
      (node (ref "E8") (pin "1") (pinfunction "I0_1") (pintype "input"))
    )
    (net (code "48") (name "AIOT0L") (class "Default")
      (node (ref "E33") (pin "1") (pinfunction "O0_1") (pintype "output"))
      (node (ref "E34") (pin "5") (pinfunction "I1_5") (pintype "input"))
    )
    (net (code "49") (name "AIOT1L") (class "Default")
      (node (ref "E30") (pin "10") (pinfunction "PRE_10") (pintype "input"))
      (node (ref "E33") (pin "2") (pinfunction "O1_2") (pintype "output"))
    )
    (net (code "50") (name "AIOT2H") (class "Default")
      (node (ref "E3") (pin "10") (pinfunction "O_10") (pintype "output"))
      (node (ref "E8") (pin "4") (pinfunction "I0_4") (pintype "input"))
    )
    (net (code "51") (name "AIOT2L") (class "Default")
      (node (ref "E3") (pin "11") (pinfunction "I_11") (pintype "input"))
      (node (ref "E33") (pin "3") (pinfunction "O2_3") (pintype "output"))
    )
    (net (code "52") (name "AIOT3H") (class "Default")
      (node (ref "E16") (pin "9") (pinfunction "I0_9") (pintype "input"))
      (node (ref "E3") (pin "6") (pinfunction "O_6") (pintype "output"))
    )
    (net (code "53") (name "AIOT3L") (class "Default")
      (node (ref "E3") (pin "5") (pinfunction "I_5") (pintype "input"))
      (node (ref "E33") (pin "4") (pinfunction "O3_4") (pintype "output"))
      (node (ref "E34") (pin "1") (pinfunction "I0_1") (pintype "input"))
    )
    (net (code "54") (name "AIOT4L") (class "Default")
      (node (ref "E33") (pin "5") (pinfunction "O4_5") (pintype "output"))
      (node (ref "E44") (pin "10") (pinfunction "B_10") (pintype "input"))
    )
    (net (code "55") (name "AIOT5L") (class "Default")
      (node (ref "E33") (pin "6") (pinfunction "O5_6") (pintype "output"))
      (node (ref "E43") (pin "1") (pinfunction "I0_1") (pintype "input"))
      (node (ref "E43") (pin "2") (pinfunction "I1_2") (pintype "input"))
      (node (ref "E43") (pin "4") (pinfunction "I0_4") (pintype "input"))
    )
    (net (code "56") (name "AIOT6L") (class "Default")
      (node (ref "E33") (pin "7") (pinfunction "O6_7") (pintype "output"))
      (node (ref "E35") (pin "10") (pinfunction "PRE_10") (pintype "input"))
    )
    (net (code "57") (name "AIOT7L") (class "Default")
      (node (ref "E13") (pin "5") (pinfunction "I1_5") (pintype "input"))
      (node (ref "E33") (pin "9") (pinfunction "O7_9") (pintype "output"))
    )
    (net (code "58") (name "AIOTL") (class "Default")
      (node (ref "E16") (pin "2") (pinfunction "I1_2") (pintype "input"))
      (node (ref "E2") (pin "8") (pinfunction "O_8") (pintype "output"))
      (node (ref "E33") (pin "12") (pinfunction "D_12") (pintype "input"))
    )
    (net (code "59") (name "AREADY") (class "Default")
      (node (ref "E12") (pin "11") (pinfunction "CLK_11") (pintype "input"))
      (node (ref "E13") (pin "11") (pinfunction "O_11") (pintype "output"))
    )
    (net (code "60") (name "AREADYH") (class "Default")
      (node (ref "E47") (pin "8") (pinfunction "CLAMP_8") (pintype "input"))
      (node (ref "J1") (pin "LL") (pinfunction "32_LL") (pintype "bidirectional"))
      (node (ref "R5") (pin "1") (pinfunction "1_1") (pintype "passive"))
      (node (ref "R6") (pin "1") (pinfunction "1_1") (pintype "passive"))
    )
    (net (code "61") (name "AREADYL") (class "Default")
      (node (ref "E4") (pin "10") (pinfunction "I1_10") (pintype "input"))
      (node (ref "E4") (pin "12") (pinfunction "I2_12") (pintype "input"))
      (node (ref "E4") (pin "13") (pinfunction "I3_13") (pintype "input"))
      (node (ref "E4") (pin "9") (pinfunction "I0_9") (pintype "input"))
      (node (ref "E47") (pin "11") (pinfunction "CLAMP_11") (pintype "input"))
      (node (ref "J1") (pin "FF") (pinfunction "28_FF") (pintype "bidirectional"))
      (node (ref "R10") (pin "1") (pinfunction "1_1") (pintype "passive"))
    )
    (net (code "62") (name "ASTROBEH") (class "Default")
      (node (ref "E42") (pin "11") (pinfunction "O_11") (pintype "output"))
      (node (ref "E47") (pin "9") (pinfunction "CLAMP_9") (pintype "input"))
      (node (ref "J1") (pin "JJ") (pinfunction "30_JJ") (pintype "bidirectional"))
    )
    (net (code "63") (name "ASTROBEL") (class "Default")
      (node (ref "E42") (pin "6") (pinfunction "O_6") (pintype "output"))
      (node (ref "E47") (pin "12") (pinfunction "CLAMP_12") (pintype "input"))
      (node (ref "J1") (pin "DD") (pinfunction "26_DD") (pintype "bidirectional"))
    )
    (net (code "64") (name "BCTLFLGH") (class "Default")
      (node (ref "E31") (pin "2") (pinfunction "I1_2") (pintype "input"))
      (node (ref "E35") (pin "5") (pinfunction "Q_5") (pintype "output"))
    )
    (net (code "65") (name "BD00") (class "Default")
      (node (ref "E5") (pin "11") (pinfunction "O1_11") (pintype "input"))
      (node (ref "E6") (pin "15") (pinfunction "Q4_15") (pintype "output"))
    )
    (net (code "66") (name "BD00H") (class "Default")
      (node (ref "E17") (pin "11") (pinfunction "CLAMP_11") (pintype "input"))
      (node (ref "E7") (pin "11") (pinfunction "O_11") (pintype "output"))
      (node (ref "J2") (pin "B") (pinfunction "2_B") (pintype "bidirectional"))
    )
    (net (code "67") (name "BD00L") (class "Default")
      (node (ref "E6") (pin "14") (pinfunction "~{Q4}_14") (pintype "output"))
      (node (ref "E7") (pin "12") (pinfunction "I0_12") (pintype "input"))
      (node (ref "E7") (pin "13") (pinfunction "I1_13") (pintype "input"))
    )
    (net (code "68") (name "BD01") (class "Default")
      (node (ref "E5") (pin "14") (pinfunction "O0_14") (pintype "input"))
      (node (ref "E6") (pin "10") (pinfunction "Q3_10") (pintype "output"))
    )
    (net (code "69") (name "BD01H") (class "Default")
      (node (ref "E17") (pin "12") (pinfunction "CLAMP_12") (pintype "input"))
      (node (ref "E7") (pin "8") (pinfunction "O_8") (pintype "output"))
      (node (ref "J2") (pin "D") (pinfunction "4_D") (pintype "bidirectional"))
    )
    (net (code "70") (name "BD01L") (class "Default")
      (node (ref "E6") (pin "11") (pinfunction "~{Q3}_11") (pintype "output"))
      (node (ref "E7") (pin "10") (pinfunction "I1_10") (pintype "input"))
      (node (ref "E7") (pin "9") (pinfunction "I0_9") (pintype "input"))
    )
    (net (code "71") (name "BD02") (class "Default")
      (node (ref "E5") (pin "5") (pinfunction "O3_5") (pintype "input"))
      (node (ref "E6") (pin "2") (pinfunction "Q1_2") (pintype "output"))
    )
    (net (code "72") (name "BD02H") (class "Default")
      (node (ref "E17") (pin "8") (pinfunction "CLAMP_8") (pintype "input"))
      (node (ref "E7") (pin "6") (pinfunction "O_6") (pintype "output"))
      (node (ref "J2") (pin "F") (pinfunction "6_F") (pintype "bidirectional"))
    )
    (net (code "73") (name "BD02L") (class "Default")
      (node (ref "E6") (pin "3") (pinfunction "~{Q1}_3") (pintype "output"))
      (node (ref "E7") (pin "4") (pinfunction "I0_4") (pintype "input"))
      (node (ref "E7") (pin "5") (pinfunction "I1_5") (pintype "input"))
    )
    (net (code "74") (name "BD03") (class "Default")
      (node (ref "E5") (pin "2") (pinfunction "O2_2") (pintype "input"))
      (node (ref "E6") (pin "7") (pinfunction "Q2_7") (pintype "output"))
    )
    (net (code "75") (name "BD03H") (class "Default")
      (node (ref "E17") (pin "9") (pinfunction "CLAMP_9") (pintype "input"))
      (node (ref "E7") (pin "3") (pinfunction "O_3") (pintype "output"))
      (node (ref "J2") (pin "J") (pinfunction "8_J") (pintype "bidirectional"))
    )
    (net (code "76") (name "BD03L") (class "Default")
      (node (ref "E6") (pin "6") (pinfunction "~{Q2}_6") (pintype "output"))
      (node (ref "E7") (pin "1") (pinfunction "I0_1") (pintype "input"))
      (node (ref "E7") (pin "2") (pinfunction "I1_2") (pintype "input"))
    )
    (net (code "77") (name "BD04") (class "Default")
      (node (ref "E19") (pin "11") (pinfunction "O1_11") (pintype "input"))
      (node (ref "E20") (pin "15") (pinfunction "Q4_15") (pintype "output"))
    )
    (net (code "78") (name "BD04H") (class "Default")
      (node (ref "E21") (pin "8") (pinfunction "O_8") (pintype "output"))
      (node (ref "E22") (pin "9") (pinfunction "CLAMP_9") (pintype "input"))
      (node (ref "J2") (pin "L") (pinfunction "10_L") (pintype "bidirectional"))
    )
    (net (code "79") (name "BD04L") (class "Default")
      (node (ref "E20") (pin "14") (pinfunction "~{Q4}_14") (pintype "output"))
      (node (ref "E21") (pin "10") (pinfunction "I1_10") (pintype "input"))
      (node (ref "E21") (pin "9") (pinfunction "I0_9") (pintype "input"))
    )
    (net (code "80") (name "BD05") (class "Default")
      (node (ref "E19") (pin "14") (pinfunction "O0_14") (pintype "input"))
      (node (ref "E20") (pin "10") (pinfunction "Q3_10") (pintype "output"))
    )
    (net (code "81") (name "BD05H") (class "Default")
      (node (ref "E21") (pin "11") (pinfunction "O_11") (pintype "output"))
      (node (ref "E22") (pin "8") (pinfunction "CLAMP_8") (pintype "input"))
      (node (ref "J2") (pin "N") (pinfunction "12_N") (pintype "bidirectional"))
    )
    (net (code "82") (name "BD05L") (class "Default")
      (node (ref "E20") (pin "11") (pinfunction "~{Q3}_11") (pintype "output"))
      (node (ref "E21") (pin "12") (pinfunction "I0_12") (pintype "input"))
      (node (ref "E21") (pin "13") (pinfunction "I1_13") (pintype "input"))
    )
    (net (code "83") (name "BD06") (class "Default")
      (node (ref "E19") (pin "5") (pinfunction "O3_5") (pintype "input"))
      (node (ref "E20") (pin "2") (pinfunction "Q1_2") (pintype "output"))
    )
    (net (code "84") (name "BD06H") (class "Default")
      (node (ref "E21") (pin "6") (pinfunction "O_6") (pintype "output"))
      (node (ref "E22") (pin "11") (pinfunction "CLAMP_11") (pintype "input"))
      (node (ref "J2") (pin "R") (pinfunction "14_R") (pintype "bidirectional"))
    )
    (net (code "85") (name "BD06L") (class "Default")
      (node (ref "E20") (pin "3") (pinfunction "~{Q1}_3") (pintype "output"))
      (node (ref "E21") (pin "4") (pinfunction "I0_4") (pintype "input"))
      (node (ref "E21") (pin "5") (pinfunction "I1_5") (pintype "input"))
    )
    (net (code "86") (name "BD07") (class "Default")
      (node (ref "E19") (pin "2") (pinfunction "O2_2") (pintype "input"))
      (node (ref "E20") (pin "7") (pinfunction "Q2_7") (pintype "output"))
    )
    (net (code "87") (name "BD07H") (class "Default")
      (node (ref "E21") (pin "3") (pinfunction "O_3") (pintype "output"))
      (node (ref "E22") (pin "12") (pinfunction "CLAMP_12") (pintype "input"))
      (node (ref "J2") (pin "T") (pinfunction "16_T") (pintype "bidirectional"))
    )
    (net (code "88") (name "BD07L") (class "Default")
      (node (ref "E20") (pin "6") (pinfunction "~{Q2}_6") (pintype "output"))
      (node (ref "E21") (pin "1") (pinfunction "I0_1") (pintype "input"))
      (node (ref "E21") (pin "2") (pinfunction "I1_2") (pintype "input"))
    )
    (net (code "89") (name "BD08") (class "Default")
      (node (ref "E36") (pin "11") (pinfunction "O1_11") (pintype "input"))
      (node (ref "E37") (pin "15") (pinfunction "Q4_15") (pintype "output"))
    )
    (net (code "90") (name "BD08H") (class "Default")
      (node (ref "E38") (pin "8") (pinfunction "O_8") (pintype "output"))
      (node (ref "E46") (pin "2") (pinfunction "CLAMP_2") (pintype "input"))
      (node (ref "J2") (pin "V") (pinfunction "18_V") (pintype "bidirectional"))
    )
    (net (code "91") (name "BD08L") (class "Default")
      (node (ref "E37") (pin "14") (pinfunction "~{Q4}_14") (pintype "output"))
      (node (ref "E38") (pin "10") (pinfunction "I1_10") (pintype "input"))
      (node (ref "E38") (pin "9") (pinfunction "I0_9") (pintype "input"))
    )
    (net (code "92") (name "BD09") (class "Default")
      (node (ref "E36") (pin "14") (pinfunction "O0_14") (pintype "input"))
      (node (ref "E37") (pin "10") (pinfunction "Q3_10") (pintype "output"))
    )
    (net (code "93") (name "BD09H") (class "Default")
      (node (ref "E38") (pin "11") (pinfunction "O_11") (pintype "output"))
      (node (ref "E46") (pin "3") (pinfunction "CLAMP_3") (pintype "input"))
      (node (ref "J2") (pin "X") (pinfunction "20_X") (pintype "bidirectional"))
    )
    (net (code "94") (name "BD09L") (class "Default")
      (node (ref "E37") (pin "11") (pinfunction "~{Q3}_11") (pintype "output"))
      (node (ref "E38") (pin "12") (pinfunction "I0_12") (pintype "input"))
      (node (ref "E38") (pin "13") (pinfunction "I1_13") (pintype "input"))
    )
    (net (code "95") (name "BD10") (class "Default")
      (node (ref "E36") (pin "5") (pinfunction "O3_5") (pintype "input"))
      (node (ref "E37") (pin "2") (pinfunction "Q1_2") (pintype "output"))
    )
    (net (code "96") (name "BD10H") (class "Default")
      (node (ref "E38") (pin "6") (pinfunction "O_6") (pintype "output"))
      (node (ref "E46") (pin "7") (pinfunction "CLAMP_7") (pintype "input"))
      (node (ref "J2") (pin "Z") (pinfunction "22_Z") (pintype "bidirectional"))
    )
    (net (code "97") (name "BD10L") (class "Default")
      (node (ref "E37") (pin "3") (pinfunction "~{Q1}_3") (pintype "output"))
      (node (ref "E38") (pin "4") (pinfunction "I0_4") (pintype "input"))
      (node (ref "E38") (pin "5") (pinfunction "I1_5") (pintype "input"))
    )
    (net (code "98") (name "BD11") (class "Default")
      (node (ref "E36") (pin "2") (pinfunction "O2_2") (pintype "input"))
      (node (ref "E37") (pin "7") (pinfunction "Q2_7") (pintype "output"))
    )
    (net (code "99") (name "BD11H") (class "Default")
      (node (ref "E38") (pin "3") (pinfunction "O_3") (pintype "output"))
      (node (ref "E46") (pin "5") (pinfunction "CLAMP_5") (pintype "input"))
      (node (ref "J2") (pin "BB") (pinfunction "24_BB") (pintype "bidirectional"))
    )
    (net (code "100") (name "BD11L") (class "Default")
      (node (ref "E37") (pin "6") (pinfunction "~{Q2}_6") (pintype "output"))
      (node (ref "E38") (pin "1") (pinfunction "I0_1") (pintype "input"))
      (node (ref "E38") (pin "2") (pinfunction "I1_2") (pintype "input"))
    )
    (net (code "101") (name "BDFLAG") (class "Default")
      (node (ref "E12") (pin "5") (pinfunction "Q_5") (pintype "output"))
      (node (ref "E16") (pin "4") (pinfunction "I0_4") (pintype "input"))
      (node (ref "E8") (pin "12") (pinfunction "I0_12") (pintype "input"))
    )
    (net (code "102") (name "BDONEH") (class "Default")
      (node (ref "E23") (pin "8") (pinfunction "O_8") (pintype "output"))
      (node (ref "E48") (pin "2") (pinfunction "CLAMP_2") (pintype "input"))
      (node (ref "J2") (pin "NN") (pinfunction "34_NN") (pintype "bidirectional"))
    )
    (net (code "103") (name "BDONEL") (class "Default")
      (node (ref "E23") (pin "6") (pinfunction "O_6") (pintype "output"))
      (node (ref "E23") (pin "9") (pinfunction "I0_9") (pintype "input"))
      (node (ref "E48") (pin "5") (pinfunction "CLAMP_5") (pintype "input"))
      (node (ref "J2") (pin "RR") (pinfunction "36_RR") (pintype "bidirectional"))
    )
    (net (code "104") (name "BFLAGH") (class "Default")
      (node (ref "E43") (pin "11") (pinfunction "O_11") (pintype "output"))
      (node (ref "E48") (pin "8") (pinfunction "CLAMP_8") (pintype "input"))
      (node (ref "J2") (pin "TT") (pinfunction "38_TT") (pintype "bidirectional"))
    )
    (net (code "105") (name "BINITH") (class "Default")
      (node (ref "E27") (pin "6") (pinfunction "O_6") (pintype "output"))
      (node (ref "E48") (pin "7") (pinfunction "CLAMP_7") (pintype "input"))
      (node (ref "J2") (pin "VV") (pinfunction "40_VV") (pintype "bidirectional"))
    )
    (net (code "106") (name "BINTENH") (class "Default")
      (node (ref "E16") (pin "5") (pinfunction "I1_5") (pintype "input"))
      (node (ref "E30") (pin "5") (pinfunction "Q_5") (pintype "output"))
    )
    (net (code "107") (name "BIOT0L") (class "Default")
      (node (ref "E29") (pin "1") (pinfunction "O0_1") (pintype "output"))
      (node (ref "E34") (pin "12") (pinfunction "I0_12") (pintype "input"))
    )
    (net (code "108") (name "BIOT1L") (class "Default")
      (node (ref "E29") (pin "2") (pinfunction "O1_2") (pintype "output"))
      (node (ref "E30") (pin "4") (pinfunction "PRE_4") (pintype "input"))
    )
    (net (code "109") (name "BIOT2H") (class "Default")
      (node (ref "E3") (pin "12") (pinfunction "O_12") (pintype "output"))
      (node (ref "E8") (pin "13") (pinfunction "I1_13") (pintype "input"))
    )
    (net (code "110") (name "BIOT2L") (class "Default")
      (node (ref "E29") (pin "3") (pinfunction "O2_3") (pintype "output"))
      (node (ref "E3") (pin "13") (pinfunction "I_13") (pintype "input"))
    )
    (net (code "111") (name "BIOT3H") (class "Default")
      (node (ref "E16") (pin "13") (pinfunction "I1_13") (pintype "input"))
      (node (ref "E3") (pin "4") (pinfunction "O_4") (pintype "output"))
    )
    (net (code "112") (name "BIOT3L") (class "Default")
      (node (ref "E29") (pin "4") (pinfunction "O3_4") (pintype "output"))
      (node (ref "E3") (pin "3") (pinfunction "I_3") (pintype "input"))
      (node (ref "E34") (pin "9") (pinfunction "I0_9") (pintype "input"))
    )
    (net (code "113") (name "BIOT4L") (class "Default")
      (node (ref "E29") (pin "5") (pinfunction "O4_5") (pintype "output"))
      (node (ref "E44") (pin "2") (pinfunction "B_2") (pintype "input"))
    )
    (net (code "114") (name "BIOT5L") (class "Default")
      (node (ref "E19") (pin "7") (pinfunction "D0_7") (pintype "input"))
      (node (ref "E19") (pin "9") (pinfunction "D1_9") (pintype "input"))
      (node (ref "E29") (pin "6") (pinfunction "O5_6") (pintype "output"))
      (node (ref "E36") (pin "7") (pinfunction "D0_7") (pintype "input"))
      (node (ref "E36") (pin "9") (pinfunction "D1_9") (pintype "input"))
      (node (ref "E43") (pin "5") (pinfunction "I1_5") (pintype "input"))
      (node (ref "E5") (pin "7") (pinfunction "D0_7") (pintype "input"))
      (node (ref "E5") (pin "9") (pinfunction "D1_9") (pintype "input"))
    )
    (net (code "115") (name "BIOT6L") (class "Default")
      (node (ref "E29") (pin "7") (pinfunction "O6_7") (pintype "output"))
      (node (ref "E35") (pin "4") (pinfunction "PRE_4") (pintype "input"))
    )
    (net (code "116") (name "BIOT7L") (class "Default")
      (node (ref "E13") (pin "1") (pinfunction "I0_1") (pintype "input"))
      (node (ref "E29") (pin "9") (pinfunction "O7_9") (pintype "output"))
    )
    (net (code "117") (name "BIOTL") (class "Default")
      (node (ref "E1") (pin "8") (pinfunction "O_8") (pintype "output"))
      (node (ref "E16") (pin "1") (pinfunction "I0_1") (pintype "input"))
      (node (ref "E29") (pin "12") (pinfunction "D_12") (pintype "input"))
    )
    (net (code "118") (name "BREADY") (class "Default")
      (node (ref "E12") (pin "3") (pinfunction "CLK_3") (pintype "input"))
      (node (ref "E13") (pin "8") (pinfunction "O_8") (pintype "output"))
    )
    (net (code "119") (name "BREADYH") (class "Default")
      (node (ref "E48") (pin "3") (pinfunction "CLAMP_3") (pintype "input"))
      (node (ref "J2") (pin "LL") (pinfunction "32_LL") (pintype "bidirectional"))
      (node (ref "R3") (pin "1") (pinfunction "1_1") (pintype "passive"))
      (node (ref "R4") (pin "1") (pinfunction "1_1") (pintype "passive"))
    )
    (net (code "120") (name "BREADYL") (class "Default")
      (node (ref "E18") (pin "10") (pinfunction "I1_10") (pintype "input"))
      (node (ref "E18") (pin "12") (pinfunction "I2_12") (pintype "input"))
      (node (ref "E18") (pin "13") (pinfunction "I3_13") (pintype "input"))
      (node (ref "E18") (pin "9") (pinfunction "I0_9") (pintype "input"))
      (node (ref "E48") (pin "12") (pinfunction "CLAMP_12") (pintype "input"))
      (node (ref "J2") (pin "FF") (pinfunction "28_FF") (pintype "bidirectional"))
      (node (ref "R9") (pin "1") (pinfunction "1_1") (pintype "passive"))
    )
    (net (code "121") (name "BSTROBEH") (class "Default")
      (node (ref "E42") (pin "3") (pinfunction "O_3") (pintype "output"))
      (node (ref "E48") (pin "11") (pinfunction "CLAMP_11") (pintype "input"))
      (node (ref "J2") (pin "JJ") (pinfunction "30_JJ") (pintype "bidirectional"))
    )
    (net (code "122") (name "BSTROBEL") (class "Default")
      (node (ref "E42") (pin "8") (pinfunction "O_8") (pintype "output"))
      (node (ref "E48") (pin "9") (pinfunction "CLAMP_9") (pintype "input"))
      (node (ref "J2") (pin "DD") (pinfunction "26_DD") (pintype "bidirectional"))
    )
    (net (code "123") (name "DATA0") (class "Default")
      (node (ref "E10") (pin "4") (pinfunction "D1_4") (pintype "input"))
      (node (ref "E5") (pin "10") (pinfunction "I1_10") (pintype "output"))
      (node (ref "E6") (pin "13") (pinfunction "D4_13") (pintype "input"))
    )
    (net (code "124") (name "DATA1") (class "Default")
      (node (ref "E10") (pin "5") (pinfunction "D2_5") (pintype "input"))
      (node (ref "E5") (pin "13") (pinfunction "I0_13") (pintype "output"))
      (node (ref "E6") (pin "12") (pinfunction "D3_12") (pintype "input"))
    )
    (net (code "125") (name "DATA2") (class "Default")
      (node (ref "E10") (pin "13") (pinfunction "D4_13") (pintype "input"))
      (node (ref "E5") (pin "6") (pinfunction "I3_6") (pintype "output"))
      (node (ref "E6") (pin "4") (pinfunction "D1_4") (pintype "input"))
    )
    (net (code "126") (name "DATA3") (class "Default")
      (node (ref "E10") (pin "12") (pinfunction "D3_12") (pintype "input"))
      (node (ref "E5") (pin "3") (pinfunction "I2_3") (pintype "output"))
      (node (ref "E6") (pin "5") (pinfunction "D2_5") (pintype "input"))
    )
    (net (code "127") (name "DATA4") (class "Default")
      (node (ref "E19") (pin "10") (pinfunction "I1_10") (pintype "output"))
      (node (ref "E20") (pin "13") (pinfunction "D4_13") (pintype "input"))
      (node (ref "E25") (pin "4") (pinfunction "D1_4") (pintype "input"))
    )
    (net (code "128") (name "DATA5") (class "Default")
      (node (ref "E19") (pin "13") (pinfunction "I0_13") (pintype "output"))
      (node (ref "E20") (pin "12") (pinfunction "D3_12") (pintype "input"))
      (node (ref "E25") (pin "5") (pinfunction "D2_5") (pintype "input"))
    )
    (net (code "129") (name "DATA6") (class "Default")
      (node (ref "E19") (pin "6") (pinfunction "I3_6") (pintype "output"))
      (node (ref "E20") (pin "4") (pinfunction "D1_4") (pintype "input"))
      (node (ref "E25") (pin "13") (pinfunction "D4_13") (pintype "input"))
    )
    (net (code "130") (name "DATA7") (class "Default")
      (node (ref "E19") (pin "3") (pinfunction "I2_3") (pintype "output"))
      (node (ref "E20") (pin "5") (pinfunction "D2_5") (pintype "input"))
      (node (ref "E25") (pin "12") (pinfunction "D3_12") (pintype "input"))
    )
    (net (code "131") (name "DATA8") (class "Default")
      (node (ref "E36") (pin "10") (pinfunction "I1_10") (pintype "output"))
      (node (ref "E37") (pin "13") (pinfunction "D4_13") (pintype "input"))
      (node (ref "E40") (pin "4") (pinfunction "D1_4") (pintype "input"))
    )
    (net (code "132") (name "DATA9") (class "Default")
      (node (ref "E36") (pin "13") (pinfunction "I0_13") (pintype "output"))
      (node (ref "E37") (pin "12") (pinfunction "D3_12") (pintype "input"))
      (node (ref "E40") (pin "5") (pinfunction "D2_5") (pintype "input"))
    )
    (net (code "133") (name "DATA10") (class "Default")
      (node (ref "E36") (pin "6") (pinfunction "I3_6") (pintype "output"))
      (node (ref "E37") (pin "4") (pinfunction "D1_4") (pintype "input"))
      (node (ref "E40") (pin "13") (pinfunction "D4_13") (pintype "input"))
    )
    (net (code "134") (name "DATA11") (class "Default")
      (node (ref "E36") (pin "3") (pinfunction "I2_3") (pintype "output"))
      (node (ref "E37") (pin "5") (pinfunction "D2_5") (pintype "input"))
      (node (ref "E40") (pin "12") (pinfunction "D3_12") (pintype "input"))
    )
    (net (code "135") (name "GND") (class "Default")
      (node (ref "C1") (pin "2") (pinfunction "2_2") (pintype "passive"))
      (node (ref "C10") (pin "2") (pinfunction "2_2") (pintype "passive"))
      (node (ref "C100") (pin "-") (pinfunction "-_-") (pintype "passive"))
      (node (ref "C101") (pin "-") (pinfunction "-_-") (pintype "passive"))
      (node (ref "C102") (pin "-") (pinfunction "-_-") (pintype "passive"))
      (node (ref "C11") (pin "2") (pinfunction "2_2") (pintype "passive"))
      (node (ref "C12") (pin "2") (pinfunction "2_2") (pintype "passive"))
      (node (ref "C13") (pin "2") (pinfunction "2_2") (pintype "passive"))
      (node (ref "C14") (pin "2") (pinfunction "2_2") (pintype "passive"))
      (node (ref "C15") (pin "2") (pinfunction "2_2") (pintype "passive"))
      (node (ref "C16") (pin "2") (pinfunction "2_2") (pintype "passive"))
      (node (ref "C17") (pin "2") (pinfunction "2_2") (pintype "passive"))
      (node (ref "C18") (pin "2") (pinfunction "2_2") (pintype "passive"))
      (node (ref "C19") (pin "2") (pinfunction "2_2") (pintype "passive"))
      (node (ref "C2") (pin "2") (pinfunction "2_2") (pintype "passive"))
      (node (ref "C20") (pin "2") (pinfunction "2_2") (pintype "passive"))
      (node (ref "C21") (pin "2") (pinfunction "2_2") (pintype "passive"))
      (node (ref "C22") (pin "2") (pinfunction "2_2") (pintype "passive"))
      (node (ref "C23") (pin "2") (pinfunction "2_2") (pintype "passive"))
      (node (ref "C24") (pin "2") (pinfunction "2_2") (pintype "passive"))
      (node (ref "C25") (pin "2") (pinfunction "2_2") (pintype "passive"))
      (node (ref "C26") (pin "2") (pinfunction "2_2") (pintype "passive"))
      (node (ref "C27") (pin "2") (pinfunction "2_2") (pintype "passive"))
      (node (ref "C28") (pin "2") (pinfunction "2_2") (pintype "passive"))
      (node (ref "C29") (pin "2") (pinfunction "2_2") (pintype "passive"))
      (node (ref "C3") (pin "2") (pinfunction "2_2") (pintype "passive"))
      (node (ref "C30") (pin "2") (pinfunction "2_2") (pintype "passive"))
      (node (ref "C31") (pin "2") (pinfunction "2_2") (pintype "passive"))
      (node (ref "C32") (pin "2") (pinfunction "2_2") (pintype "passive"))
      (node (ref "C33") (pin "2") (pinfunction "2_2") (pintype "passive"))
      (node (ref "C34") (pin "2") (pinfunction "2_2") (pintype "passive"))
      (node (ref "C4") (pin "2") (pinfunction "2_2") (pintype "passive"))
      (node (ref "C5") (pin "2") (pinfunction "2_2") (pintype "passive"))
      (node (ref "C6") (pin "2") (pinfunction "2_2") (pintype "passive"))
      (node (ref "C7") (pin "2") (pinfunction "2_2") (pintype "passive"))
      (node (ref "C8") (pin "2") (pinfunction "2_2") (pintype "passive"))
      (node (ref "C9") (pin "2") (pinfunction "2_2") (pintype "passive"))
      (node (ref "E14") (pin "7") (pinfunction "FORCE0_7") (pintype "input"))
      (node (ref "E14") (pin "9") (pinfunction "FORCE0_9") (pintype "input"))
      (node (ref "E32") (pin "7") (pinfunction "FORCE0_7") (pintype "input"))
      (node (ref "E32") (pin "9") (pinfunction "FORCE0_9") (pintype "input"))
      (node (ref "E44") (pin "1") (pinfunction "A_1") (pintype "input"))
      (node (ref "E44") (pin "9") (pinfunction "A_9") (pintype "input"))
      (node (ref "J1") (pin "A") (pinfunction "1_A") (pintype "bidirectional"))
      (node (ref "J1") (pin "AA") (pinfunction "23_AA") (pintype "bidirectional"))
      (node (ref "J1") (pin "C") (pinfunction "3_C") (pintype "bidirectional"))
      (node (ref "J1") (pin "CC") (pinfunction "25_CC") (pintype "bidirectional"))
      (node (ref "J1") (pin "E") (pinfunction "5_E") (pintype "bidirectional"))
      (node (ref "J1") (pin "EE") (pinfunction "27_EE") (pintype "bidirectional"))
      (node (ref "J1") (pin "H") (pinfunction "7_H") (pintype "bidirectional"))
      (node (ref "J1") (pin "HH") (pinfunction "29_HH") (pintype "bidirectional"))
      (node (ref "J1") (pin "K") (pinfunction "9_K") (pintype "bidirectional"))
      (node (ref "J1") (pin "KK") (pinfunction "31_KK") (pintype "bidirectional"))
      (node (ref "J1") (pin "M") (pinfunction "11_M") (pintype "bidirectional"))
      (node (ref "J1") (pin "MM") (pinfunction "33_MM") (pintype "bidirectional"))
      (node (ref "J1") (pin "P") (pinfunction "13_P") (pintype "bidirectional"))
      (node (ref "J1") (pin "PP") (pinfunction "35_PP") (pintype "bidirectional"))
      (node (ref "J1") (pin "S") (pinfunction "15_S") (pintype "bidirectional"))
      (node (ref "J1") (pin "SS") (pinfunction "37_SS") (pintype "bidirectional"))
      (node (ref "J1") (pin "U") (pinfunction "17_U") (pintype "bidirectional"))
      (node (ref "J1") (pin "UU") (pinfunction "39_UU") (pintype "bidirectional"))
      (node (ref "J1") (pin "W") (pinfunction "19_W") (pintype "bidirectional"))
      (node (ref "J1") (pin "Y") (pinfunction "21_Y") (pintype "bidirectional"))
      (node (ref "J2") (pin "A") (pinfunction "1_A") (pintype "bidirectional"))
      (node (ref "J2") (pin "AA") (pinfunction "23_AA") (pintype "bidirectional"))
      (node (ref "J2") (pin "C") (pinfunction "3_C") (pintype "bidirectional"))
      (node (ref "J2") (pin "CC") (pinfunction "25_CC") (pintype "bidirectional"))
      (node (ref "J2") (pin "E") (pinfunction "5_E") (pintype "bidirectional"))
      (node (ref "J2") (pin "EE") (pinfunction "27_EE") (pintype "bidirectional"))
      (node (ref "J2") (pin "H") (pinfunction "7_H") (pintype "bidirectional"))
      (node (ref "J2") (pin "HH") (pinfunction "29_HH") (pintype "bidirectional"))
      (node (ref "J2") (pin "K") (pinfunction "9_K") (pintype "bidirectional"))
      (node (ref "J2") (pin "KK") (pinfunction "31_KK") (pintype "bidirectional"))
      (node (ref "J2") (pin "M") (pinfunction "11_M") (pintype "bidirectional"))
      (node (ref "J2") (pin "MM") (pinfunction "33_MM") (pintype "bidirectional"))
      (node (ref "J2") (pin "P") (pinfunction "13_P") (pintype "bidirectional"))
      (node (ref "J2") (pin "PP") (pinfunction "35_PP") (pintype "bidirectional"))
      (node (ref "J2") (pin "S") (pinfunction "15_S") (pintype "bidirectional"))
      (node (ref "J2") (pin "SS") (pinfunction "37_SS") (pintype "bidirectional"))
      (node (ref "J2") (pin "U") (pinfunction "17_U") (pintype "bidirectional"))
      (node (ref "J2") (pin "UU") (pinfunction "39_UU") (pintype "bidirectional"))
      (node (ref "J2") (pin "W") (pinfunction "19_W") (pintype "bidirectional"))
      (node (ref "J2") (pin "Y") (pinfunction "21_Y") (pintype "bidirectional"))
      (node (ref "R14") (pin "1") (pinfunction "1_1") (pintype "passive"))
      (node (ref "R16") (pin "1") (pinfunction "1_1") (pintype "passive"))
      (node (ref "R18") (pin "1") (pinfunction "1_1") (pintype "passive"))
      (node (ref "R2") (pin "2") (pinfunction "2_2") (pintype "passive"))
      (node (ref "R20") (pin "1") (pinfunction "1_1") (pintype "passive"))
      (node (ref "U$2") (pin "AC1") (pinfunction "1_AC1") (pintype "bidirectional"))
      (node (ref "U$2") (pin "AC2") (pinfunction "1_AC2") (pintype "bidirectional"))
      (node (ref "U$2") (pin "AF1") (pinfunction "1_AF1") (pintype "bidirectional"))
      (node (ref "U$2") (pin "AF2") (pinfunction "1_AF2") (pintype "bidirectional"))
      (node (ref "U$2") (pin "AN1") (pinfunction "1_AN1") (pintype "bidirectional"))
      (node (ref "U$2") (pin "AN2") (pinfunction "1_AN2") (pintype "bidirectional"))
      (node (ref "U$2") (pin "AT1") (pinfunction "1_AT1") (pintype "bidirectional"))
      (node (ref "U$2") (pin "AT2") (pinfunction "1_AT2") (pintype "bidirectional"))
      (node (ref "U$2") (pin "BC1") (pinfunction "1_BC1") (pintype "bidirectional"))
      (node (ref "U$2") (pin "BC2") (pinfunction "1_BC2") (pintype "bidirectional"))
      (node (ref "U$2") (pin "BF1") (pinfunction "1_BF1") (pintype "bidirectional"))
      (node (ref "U$2") (pin "BF2") (pinfunction "1_BF2") (pintype "bidirectional"))
      (node (ref "U$2") (pin "BN1") (pinfunction "1_BN1") (pintype "bidirectional"))
      (node (ref "U$2") (pin "BN2") (pinfunction "1_BN2") (pintype "bidirectional"))
      (node (ref "U$2") (pin "BT1") (pinfunction "1_BT1") (pintype "bidirectional"))
      (node (ref "U$2") (pin "BT2") (pinfunction "1_BT2") (pintype "bidirectional"))
      (node (ref "U$2") (pin "CC1") (pinfunction "1_CC1") (pintype "bidirectional"))
      (node (ref "U$2") (pin "CC2") (pinfunction "1_CC2") (pintype "bidirectional"))
      (node (ref "U$2") (pin "CF1") (pinfunction "1_CF1") (pintype "bidirectional"))
      (node (ref "U$2") (pin "CF2") (pinfunction "1_CF2") (pintype "bidirectional"))
      (node (ref "U$2") (pin "CN1") (pinfunction "1_CN1") (pintype "bidirectional"))
      (node (ref "U$2") (pin "CN2") (pinfunction "1_CN2") (pintype "bidirectional"))
      (node (ref "U$2") (pin "CT1") (pinfunction "1_CT1") (pintype "bidirectional"))
      (node (ref "U$2") (pin "CT2") (pinfunction "1_CT2") (pintype "bidirectional"))
      (node (ref "U$2") (pin "DC1") (pinfunction "1_DC1") (pintype "bidirectional"))
      (node (ref "U$2") (pin "DC2") (pinfunction "1_DC2") (pintype "bidirectional"))
      (node (ref "U$2") (pin "DF1") (pinfunction "1_DF1") (pintype "bidirectional"))
      (node (ref "U$2") (pin "DF2") (pinfunction "1_DF2") (pintype "bidirectional"))
      (node (ref "U$2") (pin "DN1") (pinfunction "1_DN1") (pintype "bidirectional"))
      (node (ref "U$2") (pin "DN2") (pinfunction "1_DN2") (pintype "bidirectional"))
      (node (ref "U$2") (pin "DT1") (pinfunction "1_DT1") (pintype "bidirectional"))
      (node (ref "U$2") (pin "DT2") (pinfunction "1_DT2") (pintype "bidirectional"))
      (node (ref "W29") (pin "1") (pinfunction "1_1") (pintype "passive"))
      (node (ref "W30") (pin "1") (pinfunction "1_1") (pintype "passive"))
      (node (ref "W31") (pin "1") (pinfunction "1_1") (pintype "passive"))
      (node (ref "W32") (pin "1") (pinfunction "1_1") (pintype "passive"))
    )
    (net (code "136") (name "INITIALIZE") (class "Default")
      (node (ref "E32") (pin "3") (pinfunction "Y2_3") (pintype "input"))
      (node (ref "U$2") (pin "CR1") (pinfunction "1_CR1") (pintype "bidirectional"))
    )
    (net (code "137") (name "INITIALIZEH") (class "Default")
      (node (ref "E27") (pin "1") (pinfunction "I0_1") (pintype "input"))
      (node (ref "E27") (pin "2") (pinfunction "I1_2") (pintype "input"))
      (node (ref "E45") (pin "4") (pinfunction "O_4") (pintype "open_collector"))
      (node (ref "R1") (pin "1") (pinfunction "1_1") (pintype "passive"))
      (node (ref "R2") (pin "1") (pinfunction "1_1") (pintype "passive"))
    )
    (net (code "138") (name "INITIALIZEL") (class "Default")
      (node (ref "E32") (pin "4") (pinfunction "A2_4") (pintype "output"))
      (node (ref "E34") (pin "10") (pinfunction "I1_10") (pintype "input"))
      (node (ref "E34") (pin "13") (pinfunction "I1_13") (pintype "input"))
      (node (ref "E34") (pin "2") (pinfunction "I1_2") (pintype "input"))
      (node (ref "E34") (pin "4") (pinfunction "I0_4") (pintype "input"))
      (node (ref "E45") (pin "5") (pinfunction "I0_5") (pintype "input"))
      (node (ref "E45") (pin "6") (pinfunction "I1_6") (pintype "input"))
    )
    (net (code "139") (name "INITL") (class "Default")
      (node (ref "E10") (pin "1") (pinfunction "CLR_1") (pintype "input"))
      (node (ref "E13") (pin "2") (pinfunction "I1_2") (pintype "input"))
      (node (ref "E13") (pin "4") (pinfunction "I0_4") (pintype "input"))
      (node (ref "E20") (pin "1") (pinfunction "CLR_1") (pintype "input"))
      (node (ref "E25") (pin "1") (pinfunction "CLR_1") (pintype "input"))
      (node (ref "E27") (pin "12") (pinfunction "I0_12") (pintype "input"))
      (node (ref "E27") (pin "13") (pinfunction "I1_13") (pintype "input"))
      (node (ref "E27") (pin "3") (pinfunction "O_3") (pintype "output"))
      (node (ref "E27") (pin "4") (pinfunction "I0_4") (pintype "input"))
      (node (ref "E27") (pin "5") (pinfunction "I1_5") (pintype "input"))
      (node (ref "E37") (pin "1") (pinfunction "CLR_1") (pintype "input"))
      (node (ref "E40") (pin "1") (pinfunction "CLR_1") (pintype "input"))
      (node (ref "E6") (pin "1") (pinfunction "CLR_1") (pintype "input"))
    )
    (net (code "140") (name "IO_PAUSEH") (class "Default")
      (node (ref "E1") (pin "5") (pinfunction "I4_5") (pintype "input"))
      (node (ref "E1") (pin "6") (pinfunction "I5_6") (pintype "input"))
      (node (ref "E14") (pin "2") (pinfunction "A1_2") (pintype "output"))
      (node (ref "E2") (pin "5") (pinfunction "I4_5") (pintype "input"))
      (node (ref "E2") (pin "6") (pinfunction "I5_6") (pintype "input"))
    )
    (net (code "141") (name "MD03H") (class "Default")
      (node (ref "E14") (pin "10") (pinfunction "A1_10") (pintype "output"))
      (node (ref "E15") (pin "13") (pinfunction "I_13") (pintype "input"))
      (node (ref "W1") (pin "1") (pinfunction "1_1") (pintype "passive"))
      (node (ref "W13") (pin "1") (pinfunction "1_1") (pintype "passive"))
    )
    (net (code "142") (name "MD03L") (class "Default")
      (node (ref "E15") (pin "12") (pinfunction "O_12") (pintype "output"))
      (node (ref "W14") (pin "1") (pinfunction "1_1") (pintype "passive"))
      (node (ref "W2") (pin "1") (pinfunction "1_1") (pintype "passive"))
    )
    (net (code "143") (name "MD04H") (class "Default")
      (node (ref "E14") (pin "6") (pinfunction "A3_6") (pintype "output"))
      (node (ref "E15") (pin "1") (pinfunction "I_1") (pintype "input"))
      (node (ref "W15") (pin "1") (pinfunction "1_1") (pintype "passive"))
      (node (ref "W3") (pin "1") (pinfunction "1_1") (pintype "passive"))
    )
    (net (code "144") (name "MD04L") (class "Default")
      (node (ref "E15") (pin "2") (pinfunction "O_2") (pintype "output"))
      (node (ref "W16") (pin "1") (pinfunction "1_1") (pintype "passive"))
      (node (ref "W4") (pin "1") (pinfunction "1_1") (pintype "passive"))
    )
    (net (code "145") (name "MD05H") (class "Default")
      (node (ref "E14") (pin "4") (pinfunction "A2_4") (pintype "output"))
      (node (ref "E15") (pin "3") (pinfunction "I_3") (pintype "input"))
      (node (ref "W17") (pin "1") (pinfunction "1_1") (pintype "passive"))
      (node (ref "W5") (pin "1") (pinfunction "1_1") (pintype "passive"))
    )
    (net (code "146") (name "MD05L") (class "Default")
      (node (ref "E15") (pin "4") (pinfunction "O_4") (pintype "output"))
      (node (ref "W18") (pin "1") (pinfunction "1_1") (pintype "passive"))
      (node (ref "W6") (pin "1") (pinfunction "1_1") (pintype "passive"))
    )
    (net (code "147") (name "MD06H") (class "Default")
      (node (ref "E14") (pin "12") (pinfunction "A2_12") (pintype "output"))
      (node (ref "E15") (pin "11") (pinfunction "I_11") (pintype "input"))
      (node (ref "W19") (pin "1") (pinfunction "1_1") (pintype "passive"))
      (node (ref "W7") (pin "1") (pinfunction "1_1") (pintype "passive"))
    )
    (net (code "148") (name "MD06L") (class "Default")
      (node (ref "E15") (pin "10") (pinfunction "O_10") (pintype "output"))
      (node (ref "W20") (pin "1") (pinfunction "1_1") (pintype "passive"))
      (node (ref "W8") (pin "1") (pinfunction "1_1") (pintype "passive"))
    )
    (net (code "149") (name "MD07H") (class "Default")
      (node (ref "E14") (pin "14") (pinfunction "A3_14") (pintype "output"))
      (node (ref "E15") (pin "9") (pinfunction "I_9") (pintype "input"))
      (node (ref "W21") (pin "1") (pinfunction "1_1") (pintype "passive"))
      (node (ref "W9") (pin "1") (pinfunction "1_1") (pintype "passive"))
    )
    (net (code "150") (name "MD07L") (class "Default")
      (node (ref "E15") (pin "8") (pinfunction "O_8") (pintype "output"))
      (node (ref "W10") (pin "1") (pinfunction "1_1") (pintype "passive"))
      (node (ref "W22") (pin "1") (pinfunction "1_1") (pintype "passive"))
    )
    (net (code "151") (name "MD08H") (class "Default")
      (node (ref "E15") (pin "5") (pinfunction "I_5") (pintype "input"))
      (node (ref "E32") (pin "2") (pinfunction "A1_2") (pintype "output"))
      (node (ref "W11") (pin "1") (pinfunction "1_1") (pintype "passive"))
      (node (ref "W23") (pin "1") (pinfunction "1_1") (pintype "passive"))
    )
    (net (code "152") (name "MD08L") (class "Default")
      (node (ref "E15") (pin "6") (pinfunction "O_6") (pintype "output"))
      (node (ref "W12") (pin "1") (pinfunction "1_1") (pintype "passive"))
      (node (ref "W24") (pin "1") (pinfunction "1_1") (pintype "passive"))
    )
    (net (code "153") (name "MD09H") (class "Default")
      (node (ref "E29") (pin "13") (pinfunction "C_13") (pintype "input"))
      (node (ref "E32") (pin "14") (pinfunction "A3_14") (pintype "output"))
      (node (ref "E33") (pin "13") (pinfunction "C_13") (pintype "input"))
    )
    (net (code "154") (name "MD10H") (class "Default")
      (node (ref "E29") (pin "14") (pinfunction "B_14") (pintype "input"))
      (node (ref "E32") (pin "12") (pinfunction "A2_12") (pintype "output"))
      (node (ref "E33") (pin "14") (pinfunction "B_14") (pintype "input"))
    )
    (net (code "155") (name "MD11H") (class "Default")
      (node (ref "E29") (pin "15") (pinfunction "A_15") (pintype "input"))
      (node (ref "E32") (pin "10") (pinfunction "A1_10") (pintype "output"))
      (node (ref "E33") (pin "15") (pinfunction "A_15") (pintype "input"))
    )
    (net (code "156") (name "Net-(E1A-I0)") (class "Default")
      (node (ref "E1") (pin "1") (pinfunction "I0_1") (pintype "input"))
      (node (ref "W13") (pin "2") (pinfunction "2_2") (pintype "passive"))
      (node (ref "W14") (pin "2") (pinfunction "2_2") (pintype "passive"))
    )
    (net (code "157") (name "Net-(E1A-I1)") (class "Default")
      (node (ref "E1") (pin "2") (pinfunction "I1_2") (pintype "input"))
      (node (ref "W19") (pin "2") (pinfunction "2_2") (pintype "passive"))
      (node (ref "W20") (pin "2") (pinfunction "2_2") (pintype "passive"))
    )
    (net (code "158") (name "Net-(E1A-I2)") (class "Default")
      (node (ref "E1") (pin "3") (pinfunction "I2_3") (pintype "input"))
      (node (ref "W17") (pin "2") (pinfunction "2_2") (pintype "passive"))
      (node (ref "W18") (pin "2") (pinfunction "2_2") (pintype "passive"))
    )
    (net (code "159") (name "Net-(E1A-I3)") (class "Default")
      (node (ref "E1") (pin "4") (pinfunction "I3_4") (pintype "input"))
      (node (ref "W15") (pin "2") (pinfunction "2_2") (pintype "passive"))
      (node (ref "W16") (pin "2") (pinfunction "2_2") (pintype "passive"))
    )
    (net (code "160") (name "Net-(E1A-I6)") (class "Default")
      (node (ref "E1") (pin "11") (pinfunction "I6_11") (pintype "input"))
      (node (ref "W23") (pin "2") (pinfunction "2_2") (pintype "passive"))
      (node (ref "W24") (pin "2") (pinfunction "2_2") (pintype "passive"))
    )
    (net (code "161") (name "Net-(E1A-I7)") (class "Default")
      (node (ref "E1") (pin "12") (pinfunction "I7_12") (pintype "input"))
      (node (ref "W21") (pin "2") (pinfunction "2_2") (pintype "passive"))
      (node (ref "W22") (pin "2") (pinfunction "2_2") (pintype "passive"))
    )
    (net (code "162") (name "Net-(E2A-I0)") (class "Default")
      (node (ref "E2") (pin "1") (pinfunction "I0_1") (pintype "input"))
      (node (ref "W5") (pin "2") (pinfunction "2_2") (pintype "passive"))
      (node (ref "W6") (pin "2") (pinfunction "2_2") (pintype "passive"))
    )
    (net (code "163") (name "Net-(E2A-I1)") (class "Default")
      (node (ref "E2") (pin "2") (pinfunction "I1_2") (pintype "input"))
      (node (ref "W1") (pin "2") (pinfunction "2_2") (pintype "passive"))
      (node (ref "W2") (pin "2") (pinfunction "2_2") (pintype "passive"))
    )
    (net (code "164") (name "Net-(E2A-I2)") (class "Default")
      (node (ref "E2") (pin "3") (pinfunction "I2_3") (pintype "input"))
      (node (ref "W7") (pin "2") (pinfunction "2_2") (pintype "passive"))
      (node (ref "W8") (pin "2") (pinfunction "2_2") (pintype "passive"))
    )
    (net (code "165") (name "Net-(E2A-I3)") (class "Default")
      (node (ref "E2") (pin "4") (pinfunction "I3_4") (pintype "input"))
      (node (ref "W3") (pin "2") (pinfunction "2_2") (pintype "passive"))
      (node (ref "W4") (pin "2") (pinfunction "2_2") (pintype "passive"))
    )
    (net (code "166") (name "Net-(E2A-I6)") (class "Default")
      (node (ref "E2") (pin "11") (pinfunction "I6_11") (pintype "input"))
      (node (ref "W10") (pin "2") (pinfunction "2_2") (pintype "passive"))
      (node (ref "W9") (pin "2") (pinfunction "2_2") (pintype "passive"))
    )
    (net (code "167") (name "Net-(E2A-I7)") (class "Default")
      (node (ref "E2") (pin "12") (pinfunction "I7_12") (pintype "input"))
      (node (ref "W11") (pin "2") (pinfunction "2_2") (pintype "passive"))
      (node (ref "W12") (pin "2") (pinfunction "2_2") (pintype "passive"))
    )
    (net (code "168") (name "Net-(E3D-I)") (class "Default")
      (node (ref "E3") (pin "9") (pinfunction "I_9") (pintype "input"))
      (node (ref "E4") (pin "6") (pinfunction "O_6") (pintype "output"))
    )
    (net (code "169") (name "Net-(E4A-I0)") (class "Default")
      (node (ref "C34") (pin "1") (pinfunction "1_1") (pintype "passive"))
      (node (ref "E4") (pin "1") (pinfunction "I0_1") (pintype "input"))
      (node (ref "E4") (pin "2") (pinfunction "I1_2") (pintype "input"))
      (node (ref "E4") (pin "4") (pinfunction "I2_4") (pintype "input"))
      (node (ref "E4") (pin "5") (pinfunction "I3_5") (pintype "input"))
      (node (ref "R6") (pin "2") (pinfunction "2_2") (pintype "passive"))
    )
    (net (code "170") (name "Net-(E8B-O)") (class "Default")
      (node (ref "E8") (pin "6") (pinfunction "O_6") (pintype "output"))
      (node (ref "E8") (pin "9") (pinfunction "I0_9") (pintype "input"))
    )
    (net (code "171") (name "Net-(E8C-I1)") (class "Default")
      (node (ref "E8") (pin "10") (pinfunction "I1_10") (pintype "input"))
      (node (ref "E8") (pin "11") (pinfunction "O_11") (pintype "output"))
    )
    (net (code "172") (name "Net-(E10A-CLK)") (class "Default")
      (node (ref "E10") (pin "9") (pinfunction "CLK_9") (pintype "input"))
      (node (ref "E16") (pin "8") (pinfunction "O_8") (pintype "output"))
      (node (ref "E25") (pin "9") (pinfunction "CLK_9") (pintype "input"))
      (node (ref "E40") (pin "9") (pinfunction "CLK_9") (pintype "input"))
    )
    (net (code "173") (name "Net-(E12A-CLR)") (class "Default")
      (node (ref "E12") (pin "1") (pinfunction "CLR_1") (pintype "input"))
      (node (ref "E23") (pin "5") (pinfunction "I1_5") (pintype "input"))
      (node (ref "E34") (pin "8") (pinfunction "O_8") (pintype "output"))
    )
    (net (code "174") (name "Net-(E12A-~{Q})") (class "Default")
      (node (ref "E12") (pin "6") (pinfunction "~{Q}_6") (pintype "output"))
      (node (ref "E23") (pin "4") (pinfunction "I0_4") (pintype "input"))
    )
    (net (code "175") (name "Net-(E12B-CLR)") (class "Default")
      (node (ref "E12") (pin "13") (pinfunction "CLR_13") (pintype "input"))
      (node (ref "E23") (pin "13") (pinfunction "I1_13") (pintype "input"))
      (node (ref "E34") (pin "3") (pinfunction "O_3") (pintype "output"))
    )
    (net (code "176") (name "Net-(E12B-~{Q})") (class "Default")
      (node (ref "E12") (pin "8") (pinfunction "~{Q}_8") (pintype "output"))
      (node (ref "E23") (pin "12") (pinfunction "I0_12") (pintype "input"))
    )
    (net (code "177") (name "Net-(E13A-O)") (class "Default")
      (node (ref "E13") (pin "3") (pinfunction "O_3") (pintype "output"))
      (node (ref "E35") (pin "1") (pinfunction "CLR_1") (pintype "input"))
    )
    (net (code "178") (name "Net-(E13B-O)") (class "Default")
      (node (ref "E13") (pin "6") (pinfunction "O_6") (pintype "output"))
      (node (ref "E35") (pin "13") (pinfunction "CLR_13") (pintype "input"))
    )
    (net (code "179") (name "Net-(E13C-I0)") (class "Default")
      (node (ref "E13") (pin "9") (pinfunction "I0_9") (pintype "input"))
      (node (ref "E31") (pin "8") (pinfunction "O_8") (pintype "output"))
    )
    (net (code "180") (name "Net-(E13C-I1)") (class "Default")
      (node (ref "E13") (pin "10") (pinfunction "I1_10") (pintype "input"))
      (node (ref "E3") (pin "2") (pinfunction "O_2") (pintype "output"))
    )
    (net (code "181") (name "Net-(E13D-I0)") (class "Default")
      (node (ref "E13") (pin "12") (pinfunction "I0_12") (pintype "input"))
      (node (ref "E31") (pin "11") (pinfunction "O_11") (pintype "output"))
    )
    (net (code "182") (name "Net-(E13D-I1)") (class "Default")
      (node (ref "E13") (pin "13") (pinfunction "I1_13") (pintype "input"))
      (node (ref "E3") (pin "8") (pinfunction "O_8") (pintype "output"))
    )
    (net (code "183") (name "Net-(E16A-O)") (class "Default")
      (node (ref "E16") (pin "3") (pinfunction "O_3") (pintype "output"))
      (node (ref "E28") (pin "11") (pinfunction "I0_11") (pintype "input"))
      (node (ref "E28") (pin "12") (pinfunction "I1_12") (pintype "input"))
    )
    (net (code "184") (name "Net-(E16B-O)") (class "Default")
      (node (ref "E16") (pin "6") (pinfunction "O_6") (pintype "output"))
      (node (ref "E27") (pin "10") (pinfunction "I1_10") (pintype "input"))
    )
    (net (code "185") (name "Net-(E16D-O)") (class "Default")
      (node (ref "E16") (pin "11") (pinfunction "O_11") (pintype "output"))
      (node (ref "E20") (pin "9") (pinfunction "CLK_9") (pintype "input"))
      (node (ref "E37") (pin "9") (pinfunction "CLK_9") (pintype "input"))
      (node (ref "E6") (pin "9") (pinfunction "CLK_9") (pintype "input"))
    )
    (net (code "186") (name "Net-(E18A-I0)") (class "Default")
      (node (ref "C33") (pin "1") (pinfunction "1_1") (pintype "passive"))
      (node (ref "E18") (pin "1") (pinfunction "I0_1") (pintype "input"))
      (node (ref "E18") (pin "2") (pinfunction "I1_2") (pintype "input"))
      (node (ref "E18") (pin "4") (pinfunction "I2_4") (pintype "input"))
      (node (ref "E18") (pin "5") (pinfunction "I3_5") (pintype "input"))
      (node (ref "R4") (pin "2") (pinfunction "2_2") (pintype "passive"))
    )
    (net (code "187") (name "Net-(E18A-O)") (class "Default")
      (node (ref "E18") (pin "6") (pinfunction "O_6") (pintype "output"))
      (node (ref "E3") (pin "1") (pinfunction "I_1") (pintype "input"))
    )
    (net (code "188") (name "Net-(E18B-O)") (class "Default")
      (node (ref "E18") (pin "8") (pinfunction "O_8") (pintype "output"))
      (node (ref "E31") (pin "9") (pinfunction "I0_9") (pintype "input"))
    )
    (net (code "189") (name "Net-(E24A-I1)") (class "Default")
      (node (ref "E24") (pin "11") (pinfunction "I0_11") (pintype "input"))
      (node (ref "E24") (pin "3") (pinfunction "I1_3") (pintype "input"))
      (node (ref "E24") (pin "5") (pinfunction "I0_5") (pintype "input"))
      (node (ref "E24") (pin "9") (pinfunction "I1_9") (pintype "input"))
      (node (ref "E39") (pin "11") (pinfunction "I0_11") (pintype "input"))
      (node (ref "E39") (pin "3") (pinfunction "I1_3") (pintype "input"))
      (node (ref "E39") (pin "5") (pinfunction "I0_5") (pintype "input"))
      (node (ref "E39") (pin "9") (pinfunction "I1_9") (pintype "input"))
      (node (ref "E43") (pin "3") (pinfunction "O_3") (pintype "output"))
      (node (ref "E9") (pin "11") (pinfunction "I0_11") (pintype "input"))
      (node (ref "E9") (pin "3") (pinfunction "I1_3") (pintype "input"))
      (node (ref "E9") (pin "5") (pinfunction "I0_5") (pintype "input"))
      (node (ref "E9") (pin "9") (pinfunction "I1_9") (pintype "input"))
    )
    (net (code "190") (name "Net-(E27C-I0)") (class "Default")
      (node (ref "E27") (pin "9") (pinfunction "I0_9") (pintype "input"))
      (node (ref "E8") (pin "3") (pinfunction "O_3") (pintype "output"))
    )
    (net (code "191") (name "Net-(E27C-O)") (class "Default")
      (node (ref "E27") (pin "8") (pinfunction "O_8") (pintype "output"))
      (node (ref "E45") (pin "2") (pinfunction "I0_2") (pintype "input"))
      (node (ref "E45") (pin "3") (pinfunction "I1_3") (pintype "input"))
    )
    (net (code "192") (name "Net-(E28A-I0)") (class "Default")
      (node (ref "E28") (pin "2") (pinfunction "I0_2") (pintype "input"))
      (node (ref "E28") (pin "3") (pinfunction "I1_3") (pintype "input"))
      (node (ref "E28") (pin "5") (pinfunction "I0_5") (pintype "input"))
      (node (ref "E28") (pin "6") (pinfunction "I1_6") (pintype "input"))
      (node (ref "E43") (pin "6") (pinfunction "O_6") (pintype "output"))
    )
    (net (code "193") (name "Net-(E28C-I0)") (class "Default")
      (node (ref "E28") (pin "8") (pinfunction "I0_8") (pintype "input"))
      (node (ref "E28") (pin "9") (pinfunction "I1_9") (pintype "input"))
      (node (ref "E8") (pin "8") (pinfunction "O_8") (pintype "output"))
    )
    (net (code "194") (name "Net-(E30A-CLR)") (class "Default")
      (node (ref "E30") (pin "1") (pinfunction "CLR_1") (pintype "input"))
      (node (ref "E34") (pin "11") (pinfunction "O_11") (pintype "output"))
    )
    (net (code "195") (name "Net-(E30B-CLR)") (class "Default")
      (node (ref "E30") (pin "13") (pinfunction "CLR_13") (pintype "input"))
      (node (ref "E34") (pin "6") (pinfunction "O_6") (pintype "output"))
    )
    (net (code "196") (name "Net-(E31A-I0)") (class "Default")
      (node (ref "E31") (pin "1") (pinfunction "I0_1") (pintype "input"))
      (node (ref "R7") (pin "1") (pinfunction "1_1") (pintype "passive"))
      (node (ref "W32") (pin "2") (pinfunction "2_2") (pintype "passive"))
    )
    (net (code "197") (name "Net-(E31A-O)") (class "Default")
      (node (ref "E31") (pin "3") (pinfunction "O_3") (pintype "output"))
      (node (ref "E43") (pin "12") (pinfunction "I0_12") (pintype "input"))
      (node (ref "E43") (pin "13") (pinfunction "I1_13") (pintype "input"))
    )
    (net (code "198") (name "Net-(E31B-I0)") (class "Default")
      (node (ref "E31") (pin "4") (pinfunction "I0_4") (pintype "input"))
      (node (ref "R8") (pin "1") (pinfunction "1_1") (pintype "passive"))
      (node (ref "W31") (pin "2") (pinfunction "2_2") (pintype "passive"))
    )
    (net (code "199") (name "Net-(E31B-O)") (class "Default")
      (node (ref "E31") (pin "6") (pinfunction "O_6") (pintype "output"))
      (node (ref "E43") (pin "10") (pinfunction "I1_10") (pintype "input"))
      (node (ref "E43") (pin "9") (pinfunction "I0_9") (pintype "input"))
    )
    (net (code "200") (name "Net-(E31C-I1)") (class "Default")
      (node (ref "E31") (pin "10") (pinfunction "I1_10") (pintype "input"))
      (node (ref "R12") (pin "1") (pinfunction "1_1") (pintype "passive"))
      (node (ref "W30") (pin "2") (pinfunction "2_2") (pintype "passive"))
    )
    (net (code "201") (name "Net-(E31D-I0)") (class "Default")
      (node (ref "E31") (pin "12") (pinfunction "I0_12") (pintype "input"))
      (node (ref "E4") (pin "8") (pinfunction "O_8") (pintype "output"))
    )
    (net (code "202") (name "Net-(E31D-I1)") (class "Default")
      (node (ref "E31") (pin "13") (pinfunction "I1_13") (pintype "input"))
      (node (ref "R11") (pin "1") (pinfunction "1_1") (pintype "passive"))
      (node (ref "W29") (pin "2") (pinfunction "2_2") (pintype "passive"))
    )
    (net (code "203") (name "Net-(E42A-I0)") (class "Default")
      (node (ref "E42") (pin "1") (pinfunction "I0_1") (pintype "input"))
      (node (ref "E42") (pin "2") (pinfunction "I1_2") (pintype "input"))
      (node (ref "E44") (pin "4") (pinfunction "~{Q}_4") (pintype "output"))
    )
    (net (code "204") (name "Net-(E42B-I0)") (class "Default")
      (node (ref "E42") (pin "4") (pinfunction "I0_4") (pintype "input"))
      (node (ref "E42") (pin "5") (pinfunction "I1_5") (pintype "input"))
      (node (ref "E44") (pin "5") (pinfunction "Q_5") (pintype "output"))
    )
    (net (code "205") (name "Net-(E42C-I0)") (class "Default")
      (node (ref "E42") (pin "10") (pinfunction "I1_10") (pintype "input"))
      (node (ref "E42") (pin "9") (pinfunction "I0_9") (pintype "input"))
      (node (ref "E44") (pin "13") (pinfunction "Q_13") (pintype "output"))
    )
    (net (code "206") (name "Net-(E42D-I0)") (class "Default")
      (node (ref "E42") (pin "12") (pinfunction "I0_12") (pintype "input"))
      (node (ref "E42") (pin "13") (pinfunction "I1_13") (pintype "input"))
      (node (ref "E44") (pin "12") (pinfunction "~{Q}_12") (pintype "output"))
    )
    (net (code "207") (name "Net-(E44A-C)") (class "Default")
      (node (ref "E44") (pin "14") (pinfunction "C_14") (pintype "input"))
      (node (ref "W27") (pin "2") (pinfunction "2_2") (pintype "passive"))
    )
    (net (code "208") (name "Net-(E44A-R{slash}C)") (class "Default")
      (node (ref "E44") (pin "15") (pinfunction "R/C_15") (pintype "input"))
      (node (ref "R21") (pin "2") (pinfunction "2_2") (pintype "passive"))
      (node (ref "W27") (pin "1") (pinfunction "1_1") (pintype "passive"))
    )
    (net (code "209") (name "Net-(E44B-C)") (class "Default")
      (node (ref "E44") (pin "6") (pinfunction "C_6") (pintype "input"))
      (node (ref "W25") (pin "2") (pinfunction "2_2") (pintype "passive"))
    )
    (net (code "210") (name "Net-(E44B-R{slash}C)") (class "Default")
      (node (ref "E44") (pin "7") (pinfunction "R/C_7") (pintype "input"))
      (node (ref "R22") (pin "2") (pinfunction "2_2") (pintype "passive"))
      (node (ref "W25") (pin "1") (pinfunction "1_1") (pintype "passive"))
    )
    (net (code "211") (name "Net-(R23-A)") (class "Default")
      (node (ref "R21") (pin "1") (pinfunction "1_1") (pintype "passive"))
      (node (ref "R23") (pin "1") (pinfunction "A_1") (pintype "passive"))
      (node (ref "W28") (pin "1") (pinfunction "1_1") (pintype "passive"))
    )
    (net (code "212") (name "Net-(R24-A)") (class "Default")
      (node (ref "R22") (pin "1") (pinfunction "1_1") (pintype "passive"))
      (node (ref "R24") (pin "1") (pinfunction "A_1") (pintype "passive"))
      (node (ref "W26") (pin "1") (pinfunction "1_1") (pintype "passive"))
    )
    (net (code "213") (name "TP3") (class "Default")
      (node (ref "E32") (pin "5") (pinfunction "Y3_5") (pintype "input"))
      (node (ref "U$2") (pin "CH2") (pinfunction "1_CH2") (pintype "bidirectional"))
    )
    (net (code "214") (name "TP3L") (class "Default")
      (node (ref "E16") (pin "10") (pinfunction "I1_10") (pintype "input"))
      (node (ref "E16") (pin "12") (pinfunction "I0_12") (pintype "input"))
      (node (ref "E32") (pin "6") (pinfunction "A3_6") (pintype "output"))
    )
    (net (code "215") (name "VCC") (class "Default")
      (node (ref "C1") (pin "1") (pinfunction "1_1") (pintype "passive"))
      (node (ref "C10") (pin "1") (pinfunction "1_1") (pintype "passive"))
      (node (ref "C100") (pin "+") (pinfunction "+_+") (pintype "passive"))
      (node (ref "C101") (pin "+") (pinfunction "+_+") (pintype "passive"))
      (node (ref "C102") (pin "+") (pinfunction "+_+") (pintype "passive"))
      (node (ref "C11") (pin "1") (pinfunction "1_1") (pintype "passive"))
      (node (ref "C12") (pin "1") (pinfunction "1_1") (pintype "passive"))
      (node (ref "C13") (pin "1") (pinfunction "1_1") (pintype "passive"))
      (node (ref "C14") (pin "1") (pinfunction "1_1") (pintype "passive"))
      (node (ref "C15") (pin "1") (pinfunction "1_1") (pintype "passive"))
      (node (ref "C16") (pin "1") (pinfunction "1_1") (pintype "passive"))
      (node (ref "C17") (pin "1") (pinfunction "1_1") (pintype "passive"))
      (node (ref "C18") (pin "1") (pinfunction "1_1") (pintype "passive"))
      (node (ref "C19") (pin "1") (pinfunction "1_1") (pintype "passive"))
      (node (ref "C2") (pin "1") (pinfunction "1_1") (pintype "passive"))
      (node (ref "C20") (pin "1") (pinfunction "1_1") (pintype "passive"))
      (node (ref "C21") (pin "1") (pinfunction "1_1") (pintype "passive"))
      (node (ref "C22") (pin "1") (pinfunction "1_1") (pintype "passive"))
      (node (ref "C23") (pin "1") (pinfunction "1_1") (pintype "passive"))
      (node (ref "C24") (pin "1") (pinfunction "1_1") (pintype "passive"))
      (node (ref "C25") (pin "1") (pinfunction "1_1") (pintype "passive"))
      (node (ref "C26") (pin "1") (pinfunction "1_1") (pintype "passive"))
      (node (ref "C27") (pin "1") (pinfunction "1_1") (pintype "passive"))
      (node (ref "C28") (pin "1") (pinfunction "1_1") (pintype "passive"))
      (node (ref "C29") (pin "1") (pinfunction "1_1") (pintype "passive"))
      (node (ref "C3") (pin "1") (pinfunction "1_1") (pintype "passive"))
      (node (ref "C30") (pin "1") (pinfunction "1_1") (pintype "passive"))
      (node (ref "C31") (pin "1") (pinfunction "1_1") (pintype "passive"))
      (node (ref "C32") (pin "1") (pinfunction "1_1") (pintype "passive"))
      (node (ref "C4") (pin "1") (pinfunction "1_1") (pintype "passive"))
      (node (ref "C5") (pin "1") (pinfunction "1_1") (pintype "passive"))
      (node (ref "C6") (pin "1") (pinfunction "1_1") (pintype "passive"))
      (node (ref "C7") (pin "1") (pinfunction "1_1") (pintype "passive"))
      (node (ref "C8") (pin "1") (pinfunction "1_1") (pintype "passive"))
      (node (ref "C9") (pin "1") (pinfunction "1_1") (pintype "passive"))
      (node (ref "R1") (pin "2") (pinfunction "2_2") (pintype "passive"))
      (node (ref "R10") (pin "2") (pinfunction "2_2") (pintype "passive"))
      (node (ref "R11") (pin "2") (pinfunction "2_2") (pintype "passive"))
      (node (ref "R12") (pin "2") (pinfunction "2_2") (pintype "passive"))
      (node (ref "R13") (pin "2") (pinfunction "2_2") (pintype "passive"))
      (node (ref "R15") (pin "2") (pinfunction "2_2") (pintype "passive"))
      (node (ref "R17") (pin "2") (pinfunction "2_2") (pintype "passive"))
      (node (ref "R19") (pin "2") (pinfunction "2_2") (pintype "passive"))
      (node (ref "R23") (pin "2") (pinfunction "S_2") (pintype "passive"))
      (node (ref "R23") (pin "3") (pinfunction "E_3") (pintype "passive"))
      (node (ref "R24") (pin "2") (pinfunction "S_2") (pintype "passive"))
      (node (ref "R24") (pin "3") (pinfunction "E_3") (pintype "passive"))
      (node (ref "R3") (pin "2") (pinfunction "2_2") (pintype "passive"))
      (node (ref "R5") (pin "2") (pinfunction "2_2") (pintype "passive"))
      (node (ref "R7") (pin "2") (pinfunction "2_2") (pintype "passive"))
      (node (ref "R8") (pin "2") (pinfunction "2_2") (pintype "passive"))
      (node (ref "R9") (pin "2") (pinfunction "2_2") (pintype "passive"))
      (node (ref "U$2") (pin "AA2") (pinfunction "1_AA2") (pintype "bidirectional"))
      (node (ref "U$2") (pin "BA2") (pinfunction "1_BA2") (pintype "bidirectional"))
      (node (ref "U$2") (pin "CA2") (pinfunction "1_CA2") (pintype "bidirectional"))
      (node (ref "W26") (pin "2") (pinfunction "2_2") (pintype "passive"))
      (node (ref "W28") (pin "2") (pinfunction "2_2") (pintype "passive"))
    )
    (net (code "216") (name "unconnected-(E29A-O8-Pad10)") (class "Default")
      (node (ref "E29") (pin "10") (pinfunction "O8_10") (pintype "output"))
    )
    (net (code "217") (name "unconnected-(E29A-O9-Pad11)") (class "Default")
      (node (ref "E29") (pin "11") (pinfunction "O9_11") (pintype "output"))
    )
    (net (code "218") (name "unconnected-(E30A-D-Pad2)") (class "Default")
      (node (ref "E30") (pin "2") (pinfunction "D_2") (pintype "input"))
    )
    (net (code "219") (name "unconnected-(E30A-~{Q}-Pad6)") (class "Default")
      (node (ref "E30") (pin "6") (pinfunction "~{Q}_6") (pintype "output"))
    )
    (net (code "220") (name "unconnected-(E30B-D-Pad12)") (class "Default")
      (node (ref "E30") (pin "12") (pinfunction "D_12") (pintype "input"))
    )
    (net (code "221") (name "unconnected-(E30B-~{Q}-Pad8)") (class "Default")
      (node (ref "E30") (pin "8") (pinfunction "~{Q}_8") (pintype "output"))
    )
    (net (code "222") (name "unconnected-(E33A-O8-Pad10)") (class "Default")
      (node (ref "E33") (pin "10") (pinfunction "O8_10") (pintype "output"))
    )
    (net (code "223") (name "unconnected-(E33A-O9-Pad11)") (class "Default")
      (node (ref "E33") (pin "11") (pinfunction "O9_11") (pintype "output"))
    )
    (net (code "224") (name "unconnected-(E35A-D-Pad2)") (class "Default")
      (node (ref "E35") (pin "2") (pinfunction "D_2") (pintype "input"))
    )
    (net (code "225") (name "unconnected-(E35A-~{Q}-Pad6)") (class "Default")
      (node (ref "E35") (pin "6") (pinfunction "~{Q}_6") (pintype "output"))
    )
    (net (code "226") (name "unconnected-(E35B-D-Pad12)") (class "Default")
      (node (ref "E35") (pin "12") (pinfunction "D_12") (pintype "input"))
    )
    (net (code "227") (name "unconnected-(E35B-~{Q}-Pad8)") (class "Default")
      (node (ref "E35") (pin "8") (pinfunction "~{Q}_8") (pintype "output"))
    )
    (net (code "228") (name "~{C0}") (class "Default")
      (node (ref "E28") (pin "4") (pinfunction "O_4") (pintype "open_collector"))
      (node (ref "U$2") (pin "CE1") (pinfunction "1_CE1") (pintype "bidirectional"))
    )
    (net (code "229") (name "~{C1}") (class "Default")
      (node (ref "E28") (pin "1") (pinfunction "O_1") (pintype "open_collector"))
      (node (ref "U$2") (pin "CH1") (pinfunction "1_CH1") (pintype "bidirectional"))
    )
    (net (code "230") (name "~{DATA0}") (class "Default")
      (node (ref "E5") (pin "12") (pinfunction "B1_12") (pintype "bidirectional"))
      (node (ref "E9") (pin "10") (pinfunction "O_10") (pintype "open_collector"))
      (node (ref "U$2") (pin "AR1") (pinfunction "1_AR1") (pintype "bidirectional"))
    )
    (net (code "231") (name "~{DATA1}") (class "Default")
      (node (ref "E5") (pin "15") (pinfunction "B0_15") (pintype "bidirectional"))
      (node (ref "E9") (pin "13") (pinfunction "O_13") (pintype "open_collector"))
      (node (ref "U$2") (pin "AS1") (pinfunction "1_AS1") (pintype "bidirectional"))
    )
    (net (code "232") (name "~{DATA2}") (class "Default")
      (node (ref "E5") (pin "4") (pinfunction "B3_4") (pintype "bidirectional"))
      (node (ref "E9") (pin "4") (pinfunction "O_4") (pintype "open_collector"))
      (node (ref "U$2") (pin "AU1") (pinfunction "1_AU1") (pintype "bidirectional"))
    )
    (net (code "233") (name "~{DATA3}") (class "Default")
      (node (ref "E5") (pin "1") (pinfunction "B2_1") (pintype "bidirectional"))
      (node (ref "E9") (pin "1") (pinfunction "O_1") (pintype "open_collector"))
      (node (ref "U$2") (pin "AV1") (pinfunction "1_AV1") (pintype "bidirectional"))
    )
    (net (code "234") (name "~{DATA4}") (class "Default")
      (node (ref "E19") (pin "12") (pinfunction "B1_12") (pintype "bidirectional"))
      (node (ref "E24") (pin "10") (pinfunction "O_10") (pintype "open_collector"))
      (node (ref "U$2") (pin "BR1") (pinfunction "1_BR1") (pintype "bidirectional"))
    )
    (net (code "235") (name "~{DATA5}") (class "Default")
      (node (ref "E19") (pin "15") (pinfunction "B0_15") (pintype "bidirectional"))
      (node (ref "E24") (pin "13") (pinfunction "O_13") (pintype "open_collector"))
      (node (ref "U$2") (pin "BS1") (pinfunction "1_BS1") (pintype "bidirectional"))
    )
    (net (code "236") (name "~{DATA6}") (class "Default")
      (node (ref "E19") (pin "4") (pinfunction "B3_4") (pintype "bidirectional"))
      (node (ref "E24") (pin "4") (pinfunction "O_4") (pintype "open_collector"))
      (node (ref "U$2") (pin "BU1") (pinfunction "1_BU1") (pintype "bidirectional"))
    )
    (net (code "237") (name "~{DATA7}") (class "Default")
      (node (ref "E19") (pin "1") (pinfunction "B2_1") (pintype "bidirectional"))
      (node (ref "E24") (pin "1") (pinfunction "O_1") (pintype "open_collector"))
      (node (ref "U$2") (pin "BV1") (pinfunction "1_BV1") (pintype "bidirectional"))
    )
    (net (code "238") (name "~{DATA8}") (class "Default")
      (node (ref "E36") (pin "12") (pinfunction "B1_12") (pintype "bidirectional"))
      (node (ref "E39") (pin "10") (pinfunction "O_10") (pintype "open_collector"))
      (node (ref "U$2") (pin "DR1") (pinfunction "1_DR1") (pintype "bidirectional"))
    )
    (net (code "239") (name "~{DATA9}") (class "Default")
      (node (ref "E36") (pin "15") (pinfunction "B0_15") (pintype "bidirectional"))
      (node (ref "E39") (pin "13") (pinfunction "O_13") (pintype "open_collector"))
      (node (ref "U$2") (pin "DS1") (pinfunction "1_DS1") (pintype "bidirectional"))
    )
    (net (code "240") (name "~{DATA10}") (class "Default")
      (node (ref "E36") (pin "4") (pinfunction "B3_4") (pintype "bidirectional"))
      (node (ref "E39") (pin "4") (pinfunction "O_4") (pintype "open_collector"))
      (node (ref "U$2") (pin "DU1") (pinfunction "1_DU1") (pintype "bidirectional"))
    )
    (net (code "241") (name "~{DATA11}") (class "Default")
      (node (ref "E36") (pin "1") (pinfunction "B2_1") (pintype "bidirectional"))
      (node (ref "E39") (pin "1") (pinfunction "O_1") (pintype "open_collector"))
      (node (ref "U$2") (pin "DV1") (pinfunction "1_DV1") (pintype "bidirectional"))
    )
    (net (code "242") (name "~{INTERNAL_IO}") (class "Default")
      (node (ref "E28") (pin "13") (pinfunction "O_13") (pintype "open_collector"))
      (node (ref "U$2") (pin "CL1") (pinfunction "1_CL1") (pintype "bidirectional"))
    )
    (net (code "243") (name "~{INT_RQST}") (class "Default")
      (node (ref "E45") (pin "1") (pinfunction "O_1") (pintype "open_collector"))
      (node (ref "U$2") (pin "CP1") (pinfunction "1_CP1") (pintype "bidirectional"))
    )
    (net (code "244") (name "~{IO_PAUSE}") (class "Default")
      (node (ref "E14") (pin "1") (pinfunction "Y1_1") (pintype "input"))
      (node (ref "U$2") (pin "CD1") (pinfunction "1_CD1") (pintype "bidirectional"))
    )
    (net (code "245") (name "~{MD03}") (class "Default")
      (node (ref "E14") (pin "11") (pinfunction "Y1_11") (pintype "input"))
      (node (ref "U$2") (pin "AP1") (pinfunction "1_AP1") (pintype "bidirectional"))
    )
    (net (code "246") (name "~{MD04}") (class "Default")
      (node (ref "E14") (pin "5") (pinfunction "Y3_5") (pintype "input"))
      (node (ref "U$2") (pin "BK1") (pinfunction "1_BK1") (pintype "bidirectional"))
    )
    (net (code "247") (name "~{MD05}") (class "Default")
      (node (ref "E14") (pin "3") (pinfunction "Y2_3") (pintype "input"))
      (node (ref "U$2") (pin "BL1") (pinfunction "1_BL1") (pintype "bidirectional"))
    )
    (net (code "248") (name "~{MD06}") (class "Default")
      (node (ref "E14") (pin "13") (pinfunction "Y2_13") (pintype "input"))
      (node (ref "U$2") (pin "BM1") (pinfunction "1_BM1") (pintype "bidirectional"))
    )
    (net (code "249") (name "~{MD07}") (class "Default")
      (node (ref "E14") (pin "15") (pinfunction "Y3_15") (pintype "input"))
      (node (ref "U$2") (pin "BP1") (pinfunction "1_BP1") (pintype "bidirectional"))
    )
    (net (code "250") (name "~{MD08}") (class "Default")
      (node (ref "E32") (pin "1") (pinfunction "Y1_1") (pintype "input"))
      (node (ref "U$2") (pin "DK1") (pinfunction "1_DK1") (pintype "bidirectional"))
    )
    (net (code "251") (name "~{MD09}") (class "Default")
      (node (ref "E32") (pin "15") (pinfunction "Y3_15") (pintype "input"))
      (node (ref "U$2") (pin "DL1") (pinfunction "1_DL1") (pintype "bidirectional"))
    )
    (net (code "252") (name "~{MD10}") (class "Default")
      (node (ref "E32") (pin "13") (pinfunction "Y2_13") (pintype "input"))
      (node (ref "U$2") (pin "DM1") (pinfunction "1_DM1") (pintype "bidirectional"))
    )
    (net (code "253") (name "~{MD11}") (class "Default")
      (node (ref "E32") (pin "11") (pinfunction "Y1_11") (pintype "input"))
      (node (ref "U$2") (pin "DP1") (pinfunction "1_DP1") (pintype "bidirectional"))
    )
    (net (code "254") (name "~{SKIP}") (class "Default")
      (node (ref "E28") (pin "10") (pinfunction "O_10") (pintype "open_collector"))
      (node (ref "U$2") (pin "CS1") (pinfunction "1_CS1") (pintype "bidirectional"))
    )
  )
)
